# 2016_FDP_ACTIONNEUR.net
KiCad netlist of a schematic drawn in Altium Designer
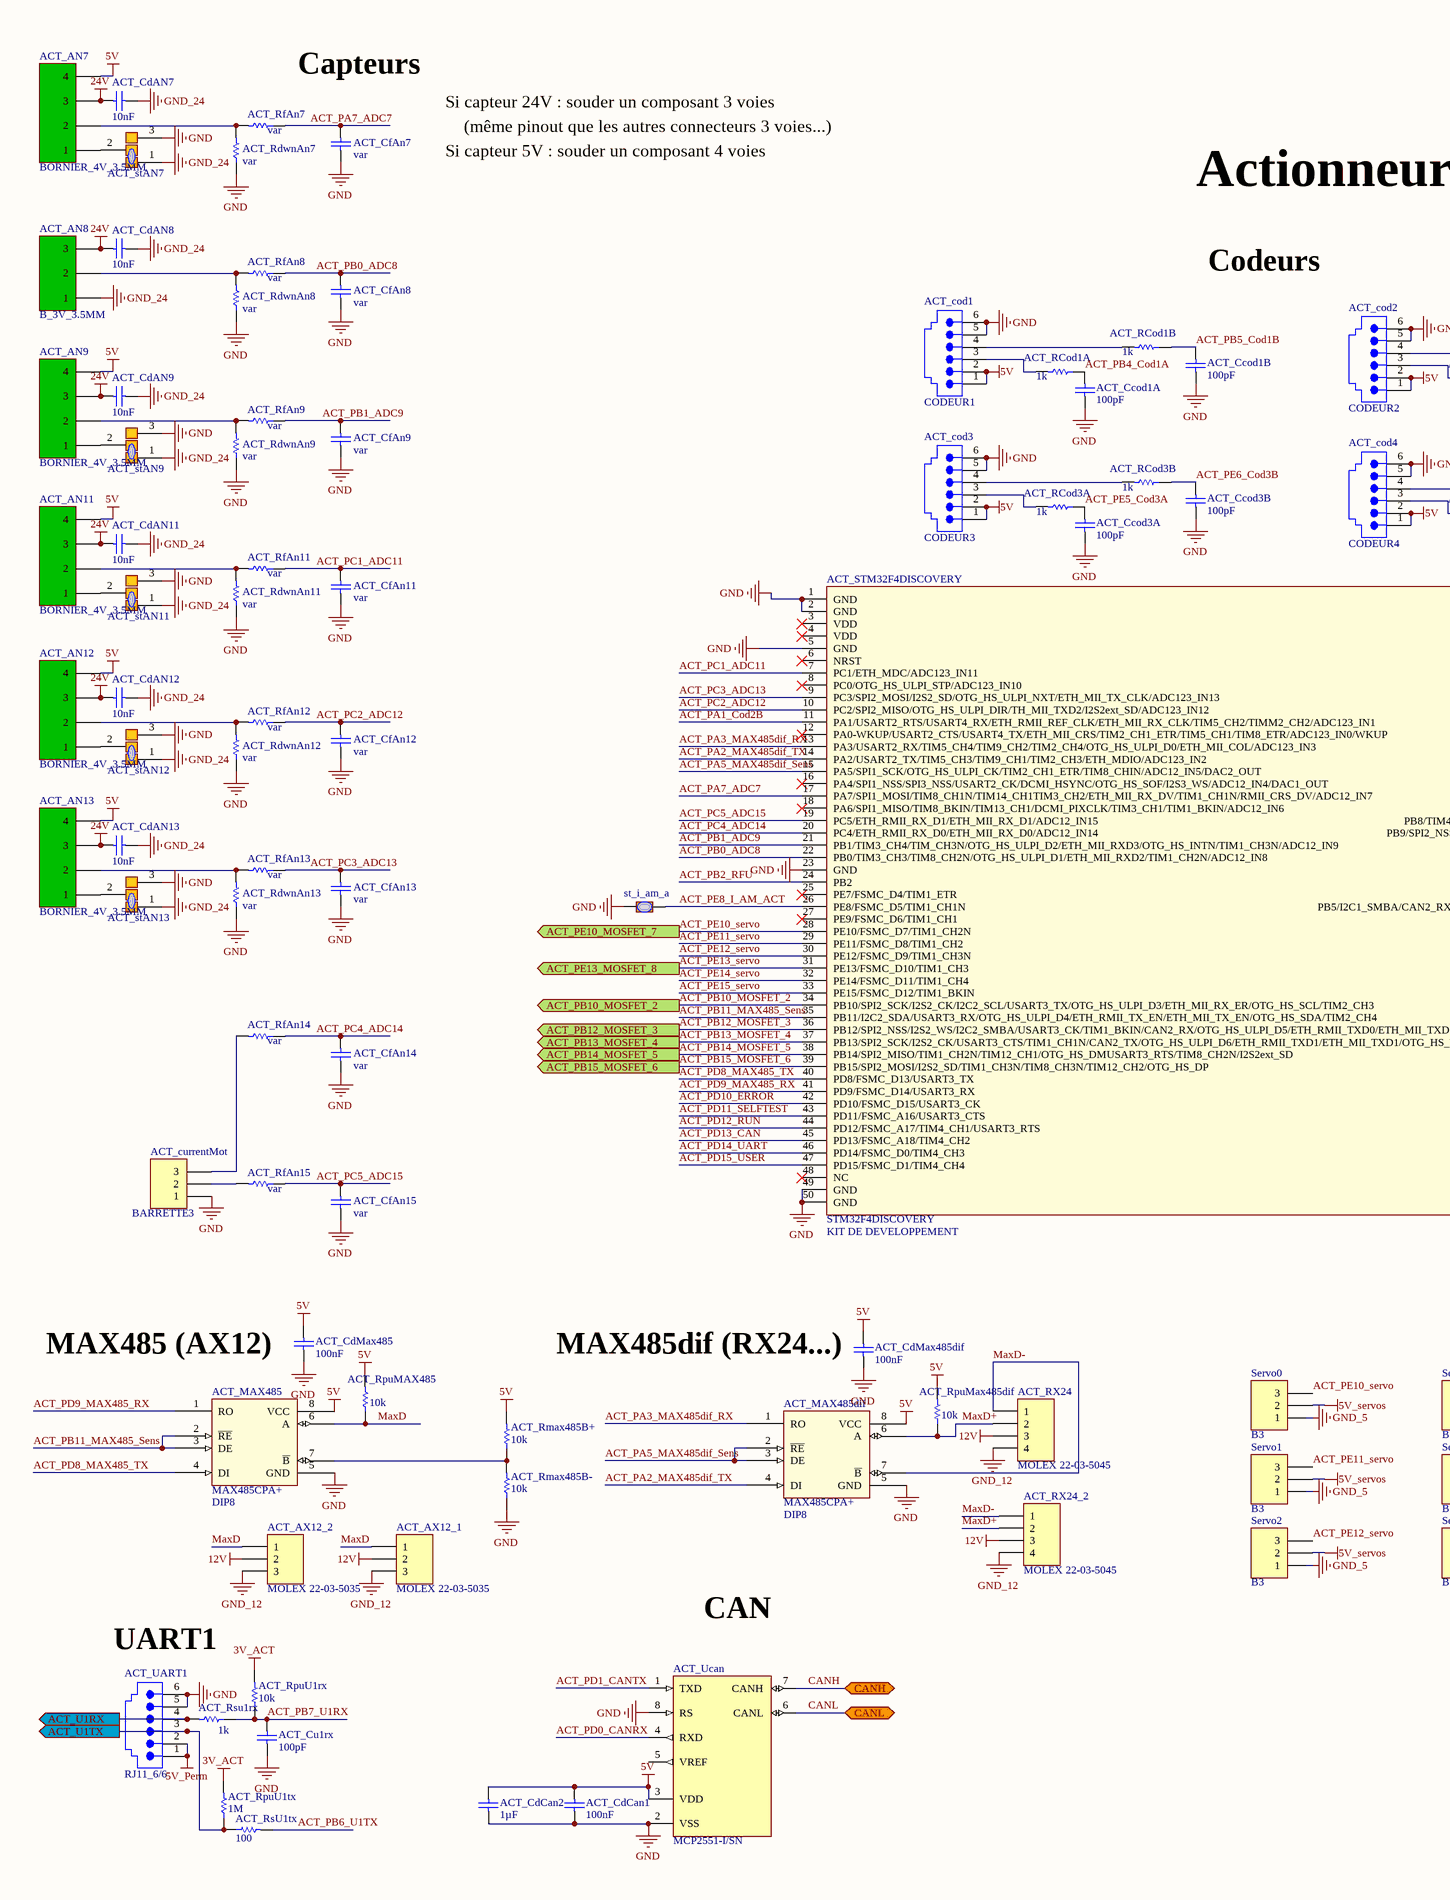
[diagram p0: 2016_FDP_ACTIONNEUR.SchDoc, left]
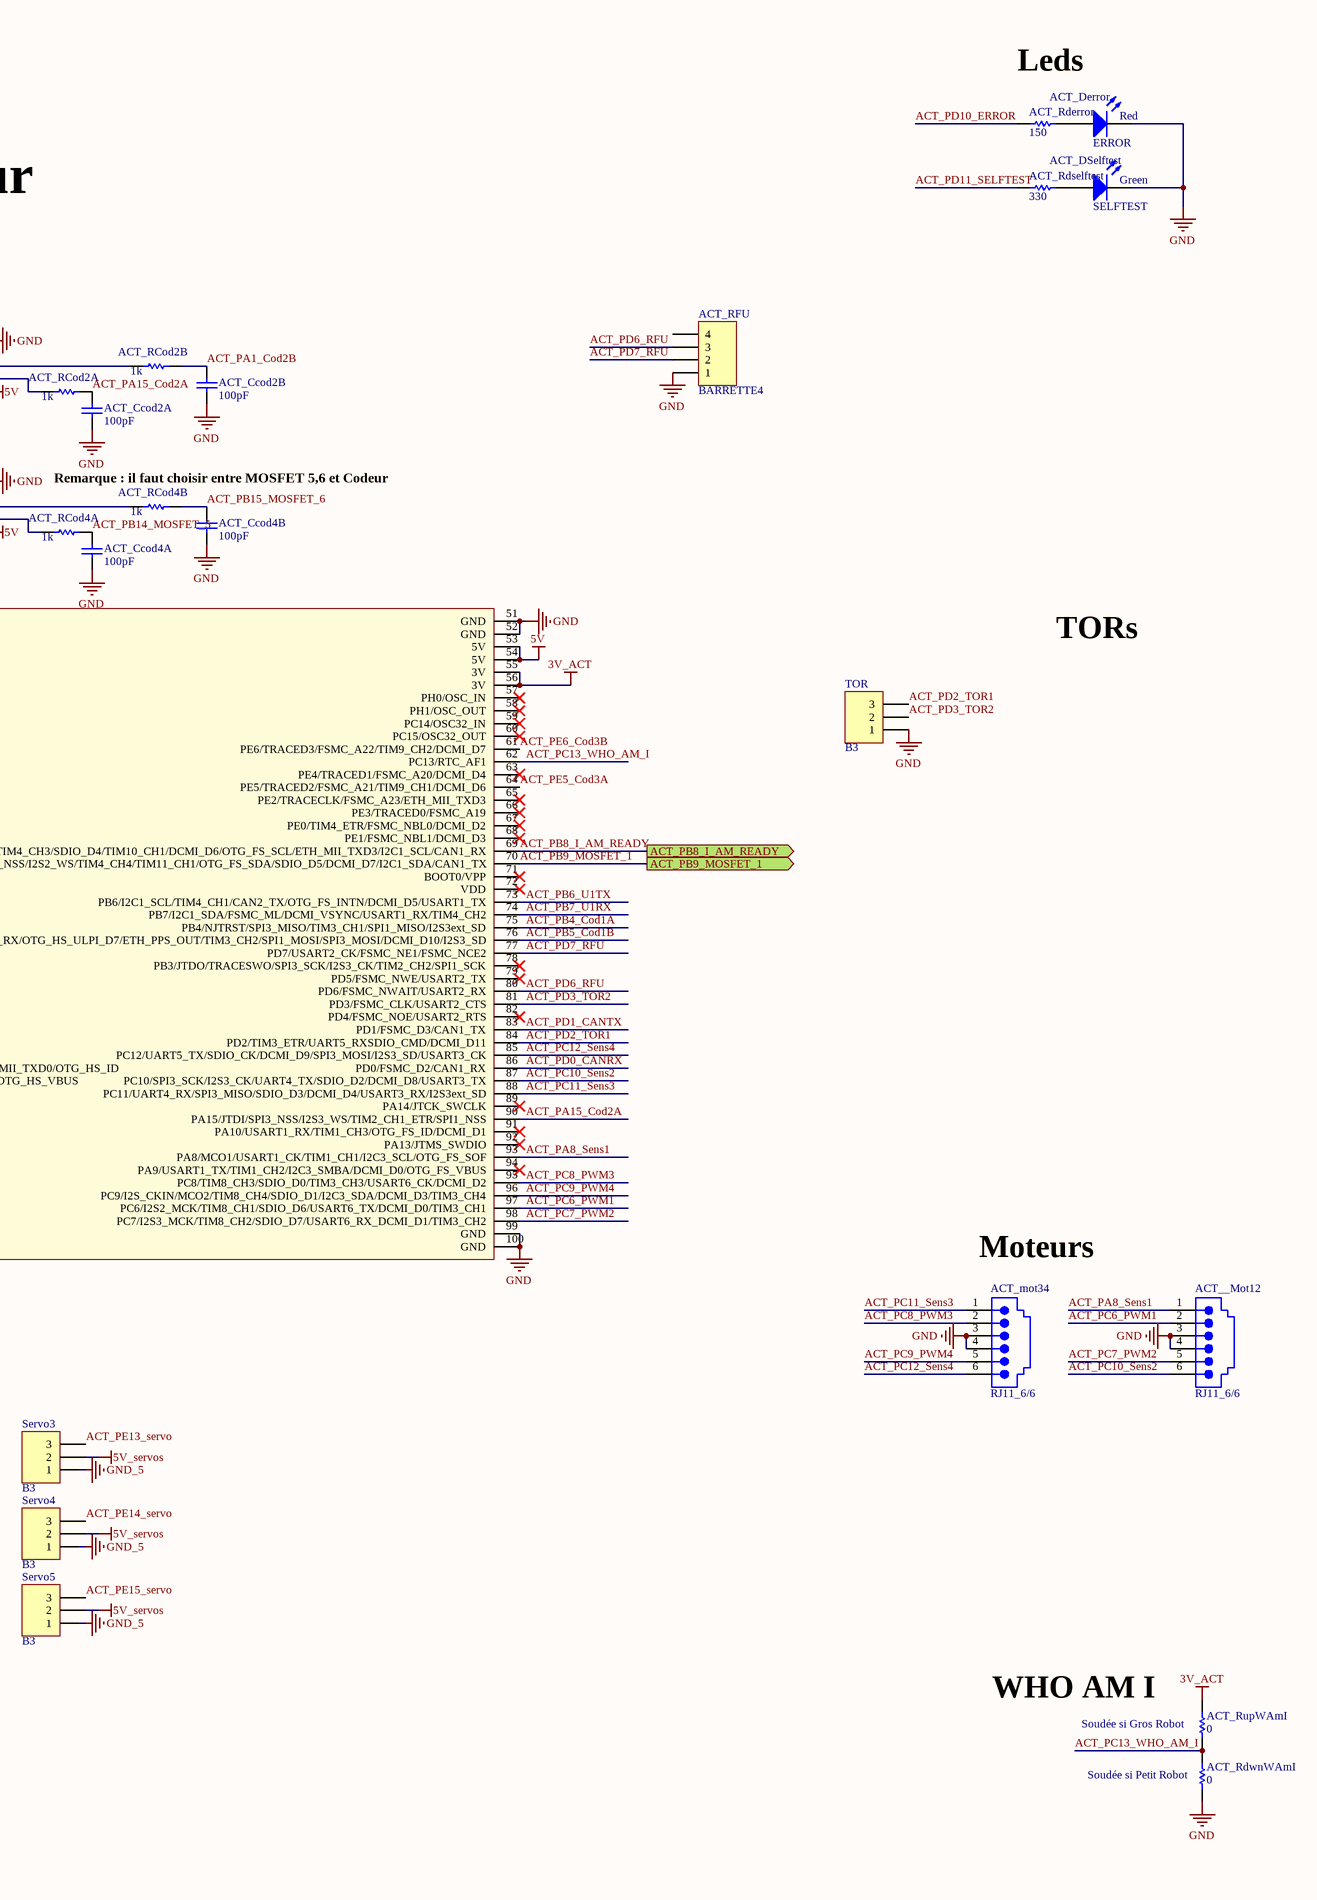
[diagram p1: 2016_FDP_ACTIONNEUR.SchDoc, right]

(export (version "E")
  (design (tool "Eeschema 10.0.6"))
  (components
    (comp (ref "ACT_AN7")
      (value "BORNIER_4V_3.5MM")
      (footprint "BORNIER_4V_3.5MM")
      (libsource (lib "Connecteur") (part "BORNIER_4V_3.5MM"))
    )
    (comp (ref "ACT_AN8")
      (value "B_3V_3.5MM")
      (footprint "BORNIER_3V_3.5MM")
      (libsource (lib "Connecteur") (part "BORNIER_3V_3.5MM"))
    )
    (comp (ref "ACT_AN9")
      (value "BORNIER_4V_3.5MM")
      (footprint "BORNIER_4V_3.5MM")
      (libsource (lib "Connecteur") (part "BORNIER_4V_3.5MM"))
    )
    (comp (ref "ACT_AN11")
      (value "BORNIER_4V_3.5MM")
      (footprint "BORNIER_4V_3.5MM")
      (libsource (lib "Connecteur") (part "BORNIER_4V_3.5MM"))
    )
    (comp (ref "ACT_AN12")
      (value "BORNIER_4V_3.5MM")
      (footprint "BORNIER_4V_3.5MM")
      (libsource (lib "Connecteur") (part "BORNIER_4V_3.5MM"))
    )
    (comp (ref "ACT_AN13")
      (value "BORNIER_4V_3.5MM")
      (footprint "BORNIER_4V_3.5MM")
      (libsource (lib "Connecteur") (part "BORNIER_4V_3.5MM"))
    )
    (comp (ref "ACT_AX12_1")
      (value "MOLEX 22-03-5035")
      (footprint "MOLEX3_2.5MM")
      (description "Header, 3-Pin")
      (fields (field (name "PUBLISHER") "Altium Limited"))
      (libsource (lib "") (part "BARRETTE3_1"))
    )
    (comp (ref "ACT_AX12_2")
      (value "MOLEX 22-03-5035")
      (footprint "MOLEX3_2.5MM")
      (description "Header, 3-Pin")
      (fields (field (name "PUBLISHER") "Altium Limited"))
      (libsource (lib "") (part "BARRETTE3_1"))
    )
    (comp (ref "ACT_Ccod1A")
      (value "100pF")
      (footprint "C0805_N")
      (description "Capacitor")
      (fields (field (name "PUBLISHER") "Altium Limited"))
      (libsource (lib "_ROBOT") (part "Condensateur"))
    )
    (comp (ref "ACT_Ccod1B")
      (value "100pF")
      (footprint "C0805_N")
      (description "Capacitor")
      (fields (field (name "PUBLISHER") "Altium Limited"))
      (libsource (lib "_ROBOT") (part "Condensateur"))
    )
    (comp (ref "ACT_Ccod2A")
      (value "100pF")
      (footprint "C0805_N")
      (description "Capacitor")
      (fields (field (name "PUBLISHER") "Altium Limited"))
      (libsource (lib "_ROBOT") (part "Condensateur"))
    )
    (comp (ref "ACT_Ccod2B")
      (value "100pF")
      (footprint "C0805_N")
      (description "Capacitor")
      (fields (field (name "PUBLISHER") "Altium Limited"))
      (libsource (lib "_ROBOT") (part "Condensateur"))
    )
    (comp (ref "ACT_Ccod3A")
      (value "100pF")
      (footprint "C0805_N")
      (description "Capacitor")
      (fields (field (name "PUBLISHER") "Altium Limited"))
      (libsource (lib "_ROBOT") (part "Condensateur"))
    )
    (comp (ref "ACT_Ccod3B")
      (value "100pF")
      (footprint "C0805_N")
      (description "Capacitor")
      (fields (field (name "PUBLISHER") "Altium Limited"))
      (libsource (lib "_ROBOT") (part "Condensateur"))
    )
    (comp (ref "ACT_Ccod4A")
      (value "100pF")
      (footprint "C0805_N")
      (description "Capacitor")
      (fields (field (name "PUBLISHER") "Altium Limited"))
      (libsource (lib "_ROBOT") (part "Condensateur"))
    )
    (comp (ref "ACT_Ccod4B")
      (value "100pF")
      (footprint "C0805_N")
      (description "Capacitor")
      (fields (field (name "PUBLISHER") "Altium Limited"))
      (libsource (lib "_ROBOT") (part "Condensateur"))
    )
    (comp (ref "ACT_CdAN7")
      (value "10nF")
      (footprint "C0805_N")
      (description "Capacitor")
      (fields (field (name "PUBLISHER") "Altium Limited"))
      (libsource (lib "_ROBOT") (part "Condensateur"))
    )
    (comp (ref "ACT_CdAN8")
      (value "10nF")
      (footprint "C0805_N")
      (description "Capacitor")
      (fields (field (name "PUBLISHER") "Altium Limited"))
      (libsource (lib "_ROBOT") (part "Condensateur"))
    )
    (comp (ref "ACT_CdAN9")
      (value "10nF")
      (footprint "C0805_N")
      (description "Capacitor")
      (fields (field (name "PUBLISHER") "Altium Limited"))
      (libsource (lib "_ROBOT") (part "Condensateur"))
    )
    (comp (ref "ACT_CdAN11")
      (value "10nF")
      (footprint "C0805_N")
      (description "Capacitor")
      (fields (field (name "PUBLISHER") "Altium Limited"))
      (libsource (lib "_ROBOT") (part "Condensateur"))
    )
    (comp (ref "ACT_CdAN12")
      (value "10nF")
      (footprint "C0805_N")
      (description "Capacitor")
      (fields (field (name "PUBLISHER") "Altium Limited"))
      (libsource (lib "_ROBOT") (part "Condensateur"))
    )
    (comp (ref "ACT_CdAN13")
      (value "10nF")
      (footprint "C0805_N")
      (description "Capacitor")
      (fields (field (name "PUBLISHER") "Altium Limited"))
      (libsource (lib "_ROBOT") (part "Condensateur"))
    )
    (comp (ref "ACT_CdCan1")
      (value "100nF")
      (footprint "C0805_N")
      (description "Capacitor")
      (fields (field (name "PUBLISHER") "Altium Limited"))
      (libsource (lib "_ROBOT") (part "Condensateur"))
    )
    (comp (ref "ACT_CdCan2")
      (value "1µF")
      (footprint "C0805_N")
      (description "Capacitor")
      (fields (field (name "PUBLISHER") "Altium Limited"))
      (libsource (lib "_ROBOT") (part "Condensateur"))
    )
    (comp (ref "ACT_CdMax485")
      (value "100nF")
      (footprint "C0805_N")
      (description "Capacitor")
      (fields (field (name "PUBLISHER") "Altium Limited"))
      (libsource (lib "_ROBOT") (part "Condensateur"))
    )
    (comp (ref "ACT_CdMax485dif")
      (value "100nF")
      (footprint "C0805_N")
      (description "Capacitor")
      (fields (field (name "PUBLISHER") "Altium Limited"))
      (libsource (lib "_ROBOT") (part "Condensateur"))
    )
    (comp (ref "ACT_CfAn7")
      (value "var")
      (footprint "C0805_N")
      (description "Capacitor")
      (fields (field (name "PUBLISHER") "Altium Limited"))
      (libsource (lib "_ROBOT") (part "Condensateur"))
    )
    (comp (ref "ACT_CfAn8")
      (value "var")
      (footprint "C0805_N")
      (description "Capacitor")
      (fields (field (name "PUBLISHER") "Altium Limited"))
      (libsource (lib "_ROBOT") (part "Condensateur"))
    )
    (comp (ref "ACT_CfAn9")
      (value "var")
      (footprint "C0805_N")
      (description "Capacitor")
      (fields (field (name "PUBLISHER") "Altium Limited"))
      (libsource (lib "_ROBOT") (part "Condensateur"))
    )
    (comp (ref "ACT_CfAn11")
      (value "var")
      (footprint "C0805_N")
      (description "Capacitor")
      (fields (field (name "PUBLISHER") "Altium Limited"))
      (libsource (lib "_ROBOT") (part "Condensateur"))
    )
    (comp (ref "ACT_CfAn12")
      (value "var")
      (footprint "C0805_N")
      (description "Capacitor")
      (fields (field (name "PUBLISHER") "Altium Limited"))
      (libsource (lib "_ROBOT") (part "Condensateur"))
    )
    (comp (ref "ACT_CfAn13")
      (value "var")
      (footprint "C0805_N")
      (description "Capacitor")
      (fields (field (name "PUBLISHER") "Altium Limited"))
      (libsource (lib "_ROBOT") (part "Condensateur"))
    )
    (comp (ref "ACT_CfAn14")
      (value "var")
      (footprint "C0805_N")
      (description "Capacitor")
      (fields (field (name "PUBLISHER") "Altium Limited"))
      (libsource (lib "_ROBOT") (part "Condensateur"))
    )
    (comp (ref "ACT_CfAn15")
      (value "var")
      (footprint "C0805_N")
      (description "Capacitor")
      (fields (field (name "PUBLISHER") "Altium Limited"))
      (libsource (lib "_ROBOT") (part "Condensateur"))
    )
    (comp (ref "ACT_cod1")
      (value "CODEUR1")
      (footprint "RJ11_6/6 - droit")
      (description "Right Angle, Standard Profile, Offset Latch DECconnect, Flangeless PCB Jack")
      (fields (field (name "PUBLISHER") "Altium Limited"))
      (libsource (lib "miniprojet") (part "RJ11_6/6"))
    )
    (comp (ref "ACT_cod2")
      (value "CODEUR2")
      (footprint "RJ11_6/6 - droit")
      (description "Right Angle, Standard Profile, Offset Latch DECconnect, Flangeless PCB Jack")
      (fields (field (name "PUBLISHER") "Altium Limited"))
      (libsource (lib "miniprojet") (part "RJ11_6/6"))
    )
    (comp (ref "ACT_cod3")
      (value "CODEUR3")
      (footprint "RJ11_6/6 - droit")
      (description "Right Angle, Standard Profile, Offset Latch DECconnect, Flangeless PCB Jack")
      (fields (field (name "PUBLISHER") "Altium Limited"))
      (libsource (lib "miniprojet") (part "RJ11_6/6"))
    )
    (comp (ref "ACT_cod4")
      (value "CODEUR4")
      (footprint "RJ11_6/6 - droit")
      (description "Right Angle, Standard Profile, Offset Latch DECconnect, Flangeless PCB Jack")
      (fields (field (name "PUBLISHER") "Altium Limited"))
      (libsource (lib "miniprojet") (part "RJ11_6/6"))
    )
    (comp (ref "ACT_Cu1rx")
      (value "100pF")
      (footprint "C0805_N")
      (description "Capacitor")
      (fields (field (name "PUBLISHER") "Altium Limited"))
      (libsource (lib "_ROBOT") (part "Condensateur"))
    )
    (comp (ref "ACT_currentMot")
      (value "BARRETTE3")
      (footprint "HE14_3")
      (description "Header, 3-Pin")
      (fields (field (name "PUBLISHER") "Altium Limited"))
      (libsource (lib "Connecteur") (part "BARRETTE3"))
    )
    (comp (ref "ACT_Derror")
      (value "ERROR")
      (footprint "LED_0805")
      (description "Typical LED")
      (fields (field (name "PUBLISHER") "Altium Limited"))
      (libsource (lib "_ROBOT") (part "LED"))
    )
    (comp (ref "ACT_DSelftest")
      (value "SELFTEST")
      (footprint "LED_0805")
      (description "Typical LED")
      (fields (field (name "PUBLISHER") "Altium Limited"))
      (libsource (lib "_ROBOT") (part "LED"))
    )
    (comp (ref "ACT_MAX485")
      (value "MAX485CPA+_DIP8")
      (footprint "SO8_N")
      (description "EMETTEUR/RECEPTEUR FAIBLE PUISSANCE DE LIAISONS RS422/RS485 - DIP8")
      (fields (field (name "TYPE") "MAX485CPA+") (field (name "PACKAGE") "DIP8"))
      (libsource (lib "circuits integres") (part "MAX485CPA+_DIP8"))
    )
    (comp (ref "ACT_MAX485dif")
      (value "MAX485CPA+_DIP8")
      (footprint "SO8_N")
      (description "EMETTEUR/RECEPTEUR FAIBLE PUISSANCE DE LIAISONS RS422/RS485 - DIP8")
      (fields (field (name "TYPE") "MAX485CPA+") (field (name "PACKAGE") "DIP8"))
      (libsource (lib "circuits integres") (part "MAX485CPA+_DIP8"))
    )
    (comp (ref "ACT_mot34")
      (value "RJ11_6/6")
      (footprint "RJ11_6/6 - droit")
      (description "Right Angle, Standard Profile, Offset Latch DECconnect, Flangeless PCB Jack")
      (fields (field (name "PUBLISHER") "Altium Limited"))
      (libsource (lib "Connecteur") (part "RJ11_6/6"))
    )
    (comp (ref "ACT_RCod1A")
      (value "1k")
      (footprint "R1206_N")
      (description "Resistor")
      (fields (field (name "PUBLISHER") "Altium Limited"))
      (libsource (lib "_ROBOT") (part "Resistor"))
    )
    (comp (ref "ACT_RCod1B")
      (value "1k")
      (footprint "R1206_N")
      (description "Resistor")
      (fields (field (name "PUBLISHER") "Altium Limited"))
      (libsource (lib "_ROBOT") (part "Resistor"))
    )
    (comp (ref "ACT_RCod2A")
      (value "1k")
      (footprint "R1206_N")
      (description "Resistor")
      (fields (field (name "PUBLISHER") "Altium Limited"))
      (libsource (lib "_ROBOT") (part "Resistor"))
    )
    (comp (ref "ACT_RCod2B")
      (value "1k")
      (footprint "R1206_N")
      (description "Resistor")
      (fields (field (name "PUBLISHER") "Altium Limited"))
      (libsource (lib "_ROBOT") (part "Resistor"))
    )
    (comp (ref "ACT_RCod3A")
      (value "1k")
      (footprint "R1206_N")
      (description "Resistor")
      (fields (field (name "PUBLISHER") "Altium Limited"))
      (libsource (lib "_ROBOT") (part "Resistor"))
    )
    (comp (ref "ACT_RCod3B")
      (value "1k")
      (footprint "R1206_N")
      (description "Resistor")
      (fields (field (name "PUBLISHER") "Altium Limited"))
      (libsource (lib "_ROBOT") (part "Resistor"))
    )
    (comp (ref "ACT_RCod4A")
      (value "1k")
      (footprint "R1206_N")
      (description "Resistor")
      (fields (field (name "PUBLISHER") "Altium Limited"))
      (libsource (lib "_ROBOT") (part "Resistor"))
    )
    (comp (ref "ACT_RCod4B")
      (value "1k")
      (footprint "R1206_N")
      (description "Resistor")
      (fields (field (name "PUBLISHER") "Altium Limited"))
      (libsource (lib "_ROBOT") (part "Resistor"))
    )
    (comp (ref "ACT_Rderror")
      (value "150")
      (footprint "R1206_N")
      (description "Resistor")
      (fields (field (name "PUBLISHER") "Altium Limited"))
      (libsource (lib "_ROBOT") (part "Resistor"))
    )
    (comp (ref "ACT_Rdselftest")
      (value "330")
      (footprint "R1206_N")
      (description "Resistor")
      (fields (field (name "PUBLISHER") "Altium Limited"))
      (libsource (lib "_ROBOT") (part "Resistor"))
    )
    (comp (ref "ACT_RdwnAn7")
      (value "var")
      (footprint "R1206_N")
      (description "Resistor")
      (fields (field (name "PUBLISHER") "Altium Limited"))
      (libsource (lib "_ROBOT") (part "Resistor"))
    )
    (comp (ref "ACT_RdwnAn8")
      (value "var")
      (footprint "R1206_N")
      (description "Resistor")
      (fields (field (name "PUBLISHER") "Altium Limited"))
      (libsource (lib "_ROBOT") (part "Resistor"))
    )
    (comp (ref "ACT_RdwnAn9")
      (value "var")
      (footprint "R1206_N")
      (description "Resistor")
      (fields (field (name "PUBLISHER") "Altium Limited"))
      (libsource (lib "_ROBOT") (part "Resistor"))
    )
    (comp (ref "ACT_RdwnAn11")
      (value "var")
      (footprint "R1206_N")
      (description "Resistor")
      (fields (field (name "PUBLISHER") "Altium Limited"))
      (libsource (lib "_ROBOT") (part "Resistor"))
    )
    (comp (ref "ACT_RdwnAn12")
      (value "var")
      (footprint "R1206_N")
      (description "Resistor")
      (fields (field (name "PUBLISHER") "Altium Limited"))
      (libsource (lib "_ROBOT") (part "Resistor"))
    )
    (comp (ref "ACT_RdwnAn13")
      (value "var")
      (footprint "R1206_N")
      (description "Resistor")
      (fields (field (name "PUBLISHER") "Altium Limited"))
      (libsource (lib "_ROBOT") (part "Resistor"))
    )
    (comp (ref "ACT_RdwnWAmI")
      (value "0")
      (footprint "R1206_N")
      (description "Resistor")
      (fields (field (name "PUBLISHER") "Altium Limited"))
      (libsource (lib "_ROBOT") (part "Resistor"))
    )
    (comp (ref "ACT_RfAn7")
      (value "var")
      (footprint "R1206_N")
      (description "Resistor")
      (fields (field (name "PUBLISHER") "Altium Limited"))
      (libsource (lib "_ROBOT") (part "Resistor"))
    )
    (comp (ref "ACT_RfAn8")
      (value "var")
      (footprint "R1206_N")
      (description "Resistor")
      (fields (field (name "PUBLISHER") "Altium Limited"))
      (libsource (lib "_ROBOT") (part "Resistor"))
    )
    (comp (ref "ACT_RfAn9")
      (value "var")
      (footprint "R1206_N")
      (description "Resistor")
      (fields (field (name "PUBLISHER") "Altium Limited"))
      (libsource (lib "_ROBOT") (part "Resistor"))
    )
    (comp (ref "ACT_RfAn11")
      (value "var")
      (footprint "R1206_N")
      (description "Resistor")
      (fields (field (name "PUBLISHER") "Altium Limited"))
      (libsource (lib "_ROBOT") (part "Resistor"))
    )
    (comp (ref "ACT_RfAn12")
      (value "var")
      (footprint "R1206_N")
      (description "Resistor")
      (fields (field (name "PUBLISHER") "Altium Limited"))
      (libsource (lib "_ROBOT") (part "Resistor"))
    )
    (comp (ref "ACT_RfAn13")
      (value "var")
      (footprint "R1206_N")
      (description "Resistor")
      (fields (field (name "PUBLISHER") "Altium Limited"))
      (libsource (lib "_ROBOT") (part "Resistor"))
    )
    (comp (ref "ACT_RfAn14")
      (value "var")
      (footprint "R1206_N")
      (description "Resistor")
      (fields (field (name "PUBLISHER") "Altium Limited"))
      (libsource (lib "_ROBOT") (part "Resistor"))
    )
    (comp (ref "ACT_RfAn15")
      (value "var")
      (footprint "R1206_N")
      (description "Resistor")
      (fields (field (name "PUBLISHER") "Altium Limited"))
      (libsource (lib "_ROBOT") (part "Resistor"))
    )
    (comp (ref "ACT_RFU")
      (value "BARRETTE4")
      (footprint "HE14_4")
      (description "Header, 4-Pin")
      (fields (field (name "PUBLISHER") "Altium Limited"))
      (libsource (lib "Connecteur") (part "BARRETTE4"))
    )
    (comp (ref "ACT_Rmax485B+")
      (value "10k")
      (footprint "R1206_N")
      (description "Resistor")
      (fields (field (name "PUBLISHER") "Altium Limited"))
      (libsource (lib "_ROBOT") (part "Resistor"))
    )
    (comp (ref "ACT_Rmax485B-")
      (value "10k")
      (footprint "R1206_N")
      (description "Resistor")
      (fields (field (name "PUBLISHER") "Altium Limited"))
      (libsource (lib "_ROBOT") (part "Resistor"))
    )
    (comp (ref "ACT_RpuMAX485")
      (value "10k")
      (footprint "R1206_N")
      (description "Resistor")
      (fields (field (name "PUBLISHER") "Altium Limited"))
      (libsource (lib "_ROBOT") (part "Resistor"))
    )
    (comp (ref "ACT_RpuMax485dif")
      (value "10k")
      (footprint "R1206_N")
      (description "Resistor")
      (fields (field (name "PUBLISHER") "Altium Limited"))
      (libsource (lib "_ROBOT") (part "Resistor"))
    )
    (comp (ref "ACT_RpuU1rx")
      (value "10k")
      (footprint "R1206_N")
      (description "Resistor")
      (fields (field (name "PUBLISHER") "Altium Limited"))
      (libsource (lib "_ROBOT") (part "Resistor"))
    )
    (comp (ref "ACT_RpuU1tx")
      (value "1M")
      (footprint "R1206_N")
      (description "Resistor")
      (fields (field (name "PUBLISHER") "Altium Limited"))
      (libsource (lib "_ROBOT") (part "Resistor"))
    )
    (comp (ref "ACT_Rsu1rx")
      (value "1k")
      (footprint "R1206_N")
      (description "Resistor")
      (fields (field (name "PUBLISHER") "Altium Limited"))
      (libsource (lib "_ROBOT") (part "Resistor"))
    )
    (comp (ref "ACT_RsU1tx")
      (value "100")
      (footprint "R1206_N")
      (description "Resistor")
      (fields (field (name "PUBLISHER") "Altium Limited"))
      (libsource (lib "_ROBOT") (part "Resistor"))
    )
    (comp (ref "ACT_RupWAmI")
      (value "0")
      (footprint "R1206_N")
      (description "Resistor")
      (fields (field (name "PUBLISHER") "Altium Limited"))
      (libsource (lib "_ROBOT") (part "Resistor"))
    )
    (comp (ref "ACT_RX24")
      (value "MOLEX 22-03-5045")
      (footprint "MOLEX4_2.5MM")
      (description "Header, 4-Pin")
      (fields (field (name "PUBLISHER") "Altium Limited"))
      (libsource (lib "") (part "BARRETTE4_1"))
    )
    (comp (ref "ACT_RX24_2")
      (value "MOLEX 22-03-5045")
      (footprint "MOLEX4_2.5MM")
      (description "Header, 4-Pin")
      (fields (field (name "PUBLISHER") "Altium Limited"))
      (libsource (lib "") (part "BARRETTE4_1"))
    )
    (comp (ref "ACT_stAN7")
      (value "strap")
      (footprint "Goutte Strap_3")
      (description "Goutte Strap_3")
      (fields (field (name "PUBLISHER") "Damien Guitton"))
      (libsource (lib "DG_Connecteur") (part "Goutte Strap_3"))
    )
    (comp (ref "ACT_stAN9")
      (value "strap")
      (footprint "Goutte Strap_3")
      (description "Goutte Strap_3")
      (fields (field (name "PUBLISHER") "Damien Guitton"))
      (libsource (lib "DG_Connecteur") (part "Goutte Strap_3"))
    )
    (comp (ref "ACT_stAN11")
      (value "strap")
      (footprint "Goutte Strap_3")
      (description "Goutte Strap_3")
      (fields (field (name "PUBLISHER") "Damien Guitton"))
      (libsource (lib "DG_Connecteur") (part "Goutte Strap_3"))
    )
    (comp (ref "ACT_stAN12")
      (value "strap")
      (footprint "Goutte Strap_3")
      (description "Goutte Strap_3")
      (fields (field (name "PUBLISHER") "Damien Guitton"))
      (libsource (lib "DG_Connecteur") (part "Goutte Strap_3"))
    )
    (comp (ref "ACT_stAN13")
      (value "strap")
      (footprint "Goutte Strap_3")
      (description "Goutte Strap_3")
      (fields (field (name "PUBLISHER") "Damien Guitton"))
      (libsource (lib "DG_Connecteur") (part "Goutte Strap_3"))
    )
    (comp (ref "ACT_STM32F4DISCOVERY")
      (value "STM32F4DISCOVERY")
      (footprint "STM32_F4DISCOVERY")
      (description "KIT DE DEVELOPPEMENT POUR MICROCONTROLEUR STM32F407VGT6")
      (fields (field (name "TYPE") "KIT DE DEVELOPPEMENT"))
      (libsource (lib "circuits integres") (part "STM32F4DISCOVERY"))
    )
    (comp (ref "ACT_UART1")
      (value "RJ11_6/6")
      (footprint "RJ11_6/6 - droit")
      (description "Right Angle, Standard Profile, Offset Latch DECconnect, Flangeless PCB Jack")
      (fields (field (name "PUBLISHER") "Altium Limited"))
      (libsource (lib "Connecteur") (part "RJ11_6/6"))
    )
    (comp (ref "ACT_Ucan")
      (value "MCP2551-I/SN")
      (footprint "SO8_N")
      (description "High-Speed CAN Transceiver, 8-Pin SOIC, Industrial Temperature")
      (fields (field (name "PUBLISHER") "Damien Guitton"))
      (libsource (lib "Circuit intégré") (part "MCP2551-I/SN"))
    )
    (comp (ref "ACT__Mot12")
      (value "RJ11_6/6")
      (footprint "RJ11_6/6 - droit")
      (description "Right Angle, Standard Profile, Offset Latch DECconnect, Flangeless PCB Jack")
      (fields (field (name "PUBLISHER") "Altium Limited"))
      (libsource (lib "Connecteur") (part "RJ11_6/6"))
    )
    (comp (ref "Servo0")
      (value "B3")
      (footprint "HE14_3")
      (description "Header, 3-Pin")
      (fields (field (name "PUBLISHER") "Altium Limited"))
      (libsource (lib "Connecteur") (part "BARRETTE3"))
    )
    (comp (ref "Servo1")
      (value "B3")
      (footprint "HE14_3")
      (description "Header, 3-Pin")
      (fields (field (name "PUBLISHER") "Altium Limited"))
      (libsource (lib "Connecteur") (part "BARRETTE3"))
    )
    (comp (ref "Servo2")
      (value "B3")
      (footprint "HE14_3")
      (description "Header, 3-Pin")
      (fields (field (name "PUBLISHER") "Altium Limited"))
      (libsource (lib "Connecteur") (part "BARRETTE3"))
    )
    (comp (ref "Servo3")
      (value "B3")
      (footprint "HE14_3")
      (description "Header, 3-Pin")
      (fields (field (name "PUBLISHER") "Altium Limited"))
      (libsource (lib "Connecteur") (part "BARRETTE3"))
    )
    (comp (ref "Servo4")
      (value "B3")
      (footprint "HE14_3")
      (description "Header, 3-Pin")
      (fields (field (name "PUBLISHER") "Altium Limited"))
      (libsource (lib "Connecteur") (part "BARRETTE3"))
    )
    (comp (ref "Servo5")
      (value "B3")
      (footprint "HE14_3")
      (description "Header, 3-Pin")
      (fields (field (name "PUBLISHER") "Altium Limited"))
      (libsource (lib "Connecteur") (part "BARRETTE3"))
    )
    (comp (ref "st_i_am_a")
      (value "Goutte Strap_2")
      (footprint "Goutte Strap_2 Pads_Clearance 0.254mm")
      (fields (field (name "PUBLISHER") "Damien Guitton"))
      (libsource (lib "DG_Connecteur") (part "Goutte Strap_2"))
    )
    (comp (ref "TOR")
      (value "B3")
      (footprint "HE14_3")
      (description "Header, 3-Pin")
      (fields (field (name "PUBLISHER") "Altium Limited"))
      (libsource (lib "Connecteur") (part "BARRETTE3"))
    )
  )
  (nets
    (net (code "1") (name "/ACT_PA1_Cod2B") (class "Default")
      (node (ref "ACT_Ccod2B") (pin "2") (pinfunction "2_2") (pintype "passive"))
      (node (ref "ACT_RCod2B") (pin "1") (pinfunction "1_1") (pintype "passive"))
      (node (ref "ACT_STM32F4DISCOVERY") (pin "11") (pinfunction "PA1/USART2_RTS/USART4_RX/ETH_RMII_REF_CLK/ETH_MII_RX_CLK/TIM5_CH2/TIMM2_CH2/ADC123_IN1_11") (pintype "passive"))
    )
    (net (code "2") (name "/ACT_PA2_MAX485dif_TX") (class "Default")
      (node (ref "ACT_MAX485dif") (pin "4") (pinfunction "DI_4") (pintype "input"))
      (node (ref "ACT_STM32F4DISCOVERY") (pin "14") (pinfunction "PA2/USART2_TX/TIM5_CH3/TIM9_CH1/TIM2_CH3/ETH_MDIO/ADC123_IN2_14") (pintype "passive"))
    )
    (net (code "3") (name "/ACT_PA3_MAX485dif_RX") (class "Default")
      (node (ref "ACT_MAX485dif") (pin "1") (pinfunction "RO_1") (pintype "tri_state"))
      (node (ref "ACT_STM32F4DISCOVERY") (pin "13") (pinfunction "PA3/USART2_RX/TIM5_CH4/TIM9_CH2/TIM2_CH4/OTG_HS_ULPI_D0/ETH_MII_COL/ADC123_IN3_13") (pintype "passive"))
    )
    (net (code "4") (name "/ACT_PA5_MAX485dif_Sens") (class "Default")
      (node (ref "ACT_MAX485dif") (pin "2") (pinfunction "~{RE}_2") (pintype "input"))
      (node (ref "ACT_MAX485dif") (pin "3") (pinfunction "DE_3") (pintype "input"))
      (node (ref "ACT_STM32F4DISCOVERY") (pin "15") (pinfunction "PA5/SPI1_SCK/OTG_HS_ULPI_CK/TIM2_CH1_ETR/TIM8_CHIN/ADC12_IN5/DAC2_OUT_15") (pintype "passive"))
    )
    (net (code "5") (name "/ACT_PA7_ADC7") (class "Default")
      (node (ref "ACT_CfAn7") (pin "2") (pinfunction "2_2") (pintype "passive"))
      (node (ref "ACT_RfAn7") (pin "1") (pinfunction "1_1") (pintype "passive"))
      (node (ref "ACT_STM32F4DISCOVERY") (pin "17") (pinfunction "PA7/SPI1_MOSI/TIM8_CH1N/TIM14_CH1TIM3_CH2/ETH_MII_RX_DV/TIM1_CH1N/RMII_CRS_DV/ADC12_IN7_17") (pintype "passive"))
    )
    (net (code "6") (name "/ACT_PA8_Sens1") (class "Default")
      (node (ref "ACT_STM32F4DISCOVERY") (pin "93") (pinfunction "PA8/MCO1/USART1_CK/TIM1_CH1/I2C3_SCL/OTG_FS_SOF_93") (pintype "passive"))
      (node (ref "ACT__Mot12") (pin "1") (pinfunction "1_1") (pintype "passive"))
    )
    (net (code "7") (name "/ACT_PA15_Cod2A") (class "Default")
      (node (ref "ACT_Ccod2A") (pin "2") (pinfunction "2_2") (pintype "passive"))
      (node (ref "ACT_RCod2A") (pin "1") (pinfunction "1_1") (pintype "passive"))
      (node (ref "ACT_STM32F4DISCOVERY") (pin "90") (pinfunction "PA15/JTDI/SPI3_NSS/I2S3_WS/TIM2_CH1_ETR/SPI1_NSS_90") (pintype "passive"))
    )
    (net (code "8") (name "/ACT_PB0_ADC8") (class "Default")
      (node (ref "ACT_CfAn8") (pin "2") (pinfunction "2_2") (pintype "passive"))
      (node (ref "ACT_RfAn8") (pin "1") (pinfunction "1_1") (pintype "passive"))
      (node (ref "ACT_STM32F4DISCOVERY") (pin "22") (pinfunction "PB0/TIM3_CH3/TIM8_CH2N/OTG_HS_ULPI_D1/ETH_MII_RXD2/TIM1_CH2N/ADC12_IN8_22") (pintype "passive"))
    )
    (net (code "9") (name "/ACT_PB1_ADC9") (class "Default")
      (node (ref "ACT_CfAn9") (pin "2") (pinfunction "2_2") (pintype "passive"))
      (node (ref "ACT_RfAn9") (pin "1") (pinfunction "1_1") (pintype "passive"))
      (node (ref "ACT_STM32F4DISCOVERY") (pin "21") (pinfunction "PB1/TIM3_CH4/TIM_CH3N/OTG_HS_ULPI_D2/ETH_MII_RXD3/OTG_HS_INTN/TIM1_CH3N/ADC12_IN9_21") (pintype "passive"))
    )
    (net (code "10") (name "/ACT_PB2_RFU") (class "Default")
      (node (ref "ACT_STM32F4DISCOVERY") (pin "24") (pinfunction "PB2_24") (pintype "passive"))
    )
    (net (code "11") (name "/ACT_PB4_Cod1A") (class "Default")
      (node (ref "ACT_Ccod1A") (pin "2") (pinfunction "2_2") (pintype "passive"))
      (node (ref "ACT_RCod1A") (pin "1") (pinfunction "1_1") (pintype "passive"))
      (node (ref "ACT_STM32F4DISCOVERY") (pin "75") (pinfunction "PB4/NJTRST/SPI3_MISO/TIM3_CH1/SPI1_MISO/I2S3ext_SD_75") (pintype "passive"))
    )
    (net (code "12") (name "/ACT_PB5_Cod1B") (class "Default")
      (node (ref "ACT_Ccod1B") (pin "2") (pinfunction "2_2") (pintype "passive"))
      (node (ref "ACT_RCod1B") (pin "1") (pinfunction "1_1") (pintype "passive"))
      (node (ref "ACT_STM32F4DISCOVERY") (pin "76") (pinfunction "PB5/I2C1_SMBA/CAN2_RX/OTG_HS_ULPI_D7/ETH_PPS_OUT/TIM3_CH2/SPI1_MOSI/SPI3_MOSI/DCMI_D10/I2S3_SD_76") (pintype "passive"))
    )
    (net (code "13") (name "/ACT_PB6_U1TX") (class "Default")
      (node (ref "ACT_RsU1tx") (pin "2") (pinfunction "2_2") (pintype "passive"))
      (node (ref "ACT_STM32F4DISCOVERY") (pin "73") (pinfunction "PB6/I2C1_SCL/TIM4_CH1/CAN2_TX/OTG_FS_INTN/DCMI_D5/USART1_TX_73") (pintype "passive"))
    )
    (net (code "14") (name "/ACT_PB7_U1RX") (class "Default")
      (node (ref "ACT_Cu1rx") (pin "2") (pinfunction "2_2") (pintype "passive"))
      (node (ref "ACT_RpuU1rx") (pin "1") (pinfunction "1_1") (pintype "passive"))
      (node (ref "ACT_Rsu1rx") (pin "1") (pinfunction "1_1") (pintype "passive"))
      (node (ref "ACT_STM32F4DISCOVERY") (pin "74") (pinfunction "PB7/I2C1_SDA/FSMC_ML/DCMI_VSYNC/USART1_RX/TIM4_CH2_74") (pintype "passive"))
    )
    (net (code "15") (name "/ACT_PB8_I_AM_READY") (class "Default")
      (node (ref "ACT_STM32F4DISCOVERY") (pin "69") (pinfunction "PB8/TIM4_CH3/SDIO_D4/TIM10_CH1/DCMI_D6/OTG_FS_SCL/ETH_MII_TXD3/I2C1_SCL/CAN1_RX_69") (pintype "passive"))
    )
    (net (code "16") (name "/ACT_PB9_MOSFET_1") (class "Default")
      (node (ref "ACT_STM32F4DISCOVERY") (pin "70") (pinfunction "PB9/SPI2_NSS/I2S2_WS/TIM4_CH4/TIM11_CH1/OTG_FS_SDA/SDIO_D5/DCMI_D7/I2C1_SDA/CAN1_TX_70") (pintype "passive"))
    )
    (net (code "17") (name "/ACT_PB10_MOSFET_2") (class "Default")
      (node (ref "ACT_STM32F4DISCOVERY") (pin "34") (pinfunction "PB10/SPI2_SCK/I2S2_CK/I2C2_SCL/USART3_TX/OTG_HS_ULPI_D3/ETH_MII_RX_ER/OTG_HS_SCL/TIM2_CH3_34") (pintype "passive"))
    )
    (net (code "18") (name "/ACT_PB11_MAX485_Sens") (class "Default")
      (node (ref "ACT_MAX485") (pin "2") (pinfunction "~{RE}_2") (pintype "input"))
      (node (ref "ACT_MAX485") (pin "3") (pinfunction "DE_3") (pintype "input"))
      (node (ref "ACT_STM32F4DISCOVERY") (pin "35") (pinfunction "PB11/I2C2_SDA/USART3_RX/OTG_HS_ULPI_D4/ETH_RMII_TX_EN/ETH_MII_TX_EN/OTG_HS_SDA/TIM2_CH4_35") (pintype "passive"))
    )
    (net (code "19") (name "/ACT_PB12_MOSFET_3") (class "Default")
      (node (ref "ACT_STM32F4DISCOVERY") (pin "36") (pinfunction "PB12/SPI2_NSS/I2S2_WS/I2C2_SMBA/USART3_CK/TIM1_BKIN/CAN2_RX/OTG_HS_ULPI_D5/ETH_RMII_TXD0/ETH_MII_TXD0/OTG_HS_ID_36") (pintype "passive"))
    )
    (net (code "20") (name "/ACT_PB13_MOSFET_4") (class "Default")
      (node (ref "ACT_STM32F4DISCOVERY") (pin "37") (pinfunction "PB13/SPI2_SCK/I2S2_CK/USART3_CTS/TIM1_CH1N/CAN2_TX/OTG_HS_ULPI_D6/ETH_RMII_TXD1/ETH_MII_TXD1/OTG_HS_VBUS_37") (pintype "passive"))
    )
    (net (code "21") (name "/ACT_PB14_MOSFET_5") (class "Default")
      (node (ref "ACT_Ccod4A") (pin "2") (pinfunction "2_2") (pintype "passive"))
      (node (ref "ACT_RCod4A") (pin "1") (pinfunction "1_1") (pintype "passive"))
      (node (ref "ACT_STM32F4DISCOVERY") (pin "38") (pinfunction "PB14/SPI2_MISO/TIM1_CH2N/TIM12_CH1/OTG_HS_DMUSART3_RTS/TIM8_CH2N/I2S2ext_SD_38") (pintype "passive"))
    )
    (net (code "22") (name "/ACT_PB15_MOSFET_6") (class "Default")
      (node (ref "ACT_Ccod4B") (pin "2") (pinfunction "2_2") (pintype "passive"))
      (node (ref "ACT_RCod4B") (pin "1") (pinfunction "1_1") (pintype "passive"))
      (node (ref "ACT_STM32F4DISCOVERY") (pin "39") (pinfunction "PB15/SPI2_MOSI/I2S2_SD/TIM1_CH3N/TIM8_CH3N/TIM12_CH2/OTG_HS_DP_39") (pintype "passive"))
    )
    (net (code "23") (name "/ACT_PC1_ADC11") (class "Default")
      (node (ref "ACT_CfAn11") (pin "2") (pinfunction "2_2") (pintype "passive"))
      (node (ref "ACT_RfAn11") (pin "1") (pinfunction "1_1") (pintype "passive"))
      (node (ref "ACT_STM32F4DISCOVERY") (pin "7") (pinfunction "PC1/ETH_MDC/ADC123_IN11_7") (pintype "passive"))
    )
    (net (code "24") (name "/ACT_PC2_ADC12") (class "Default")
      (node (ref "ACT_CfAn12") (pin "2") (pinfunction "2_2") (pintype "passive"))
      (node (ref "ACT_RfAn12") (pin "1") (pinfunction "1_1") (pintype "passive"))
      (node (ref "ACT_STM32F4DISCOVERY") (pin "10") (pinfunction "PC2/SPI2_MISO/OTG_HS_ULPI_DIR/TH_MII_TXD2/I2S2ext_SD/ADC123_IN12_10") (pintype "passive"))
    )
    (net (code "25") (name "/ACT_PC3_ADC13") (class "Default")
      (node (ref "ACT_CfAn13") (pin "2") (pinfunction "2_2") (pintype "passive"))
      (node (ref "ACT_RfAn13") (pin "1") (pinfunction "1_1") (pintype "passive"))
      (node (ref "ACT_STM32F4DISCOVERY") (pin "9") (pinfunction "PC3/SPI2_MOSI/I2S2_SD/OTG_HS_ULPI_NXT/ETH_MII_TX_CLK/ADC123_IN13_9") (pintype "passive"))
    )
    (net (code "26") (name "/ACT_PC4_ADC14") (class "Default")
      (node (ref "ACT_CfAn14") (pin "2") (pinfunction "2_2") (pintype "passive"))
      (node (ref "ACT_RfAn14") (pin "1") (pinfunction "1_1") (pintype "passive"))
      (node (ref "ACT_STM32F4DISCOVERY") (pin "20") (pinfunction "PC4/ETH_RMII_RX_D0/ETH_MII_RX_D0/ADC12_IN14_20") (pintype "passive"))
    )
    (net (code "27") (name "/ACT_PC5_ADC15") (class "Default")
      (node (ref "ACT_CfAn15") (pin "2") (pinfunction "2_2") (pintype "passive"))
      (node (ref "ACT_RfAn15") (pin "1") (pinfunction "1_1") (pintype "passive"))
      (node (ref "ACT_STM32F4DISCOVERY") (pin "19") (pinfunction "PC5/ETH_RMII_RX_D1/ETH_MII_RX_D1/ADC12_IN15_19") (pintype "passive"))
    )
    (net (code "28") (name "/ACT_PC6_PWM1") (class "Default")
      (node (ref "ACT_STM32F4DISCOVERY") (pin "97") (pinfunction "PC6/I2S2_MCK/TIM8_CH1/SDIO_D6/USART6_TX/DCMI_D0/TIM3_CH1_97") (pintype "passive"))
      (node (ref "ACT__Mot12") (pin "2") (pinfunction "2_2") (pintype "passive"))
    )
    (net (code "29") (name "/ACT_PC7_PWM2") (class "Default")
      (node (ref "ACT_STM32F4DISCOVERY") (pin "98") (pinfunction "PC7/I2S3_MCK/TIM8_CH2/SDIO_D7/USART6_RX_DCMI_D1/TIM3_CH2_98") (pintype "passive"))
      (node (ref "ACT__Mot12") (pin "5") (pinfunction "5_5") (pintype "passive"))
    )
    (net (code "30") (name "/ACT_PC8_PWM3") (class "Default")
      (node (ref "ACT_STM32F4DISCOVERY") (pin "95") (pinfunction "PC8/TIM8_CH3/SDIO_D0/TIM3_CH3/USART6_CK/DCMI_D2_95") (pintype "passive"))
      (node (ref "ACT_mot34") (pin "2") (pinfunction "2_2") (pintype "passive"))
    )
    (net (code "31") (name "/ACT_PC9_PWM4") (class "Default")
      (node (ref "ACT_STM32F4DISCOVERY") (pin "96") (pinfunction "PC9/I2S_CKIN/MCO2/TIM8_CH4/SDIO_D1/I2C3_SDA/DCMI_D3/TIM3_CH4_96") (pintype "passive"))
      (node (ref "ACT_mot34") (pin "5") (pinfunction "5_5") (pintype "passive"))
    )
    (net (code "32") (name "/ACT_PC10_Sens2") (class "Default")
      (node (ref "ACT_STM32F4DISCOVERY") (pin "87") (pinfunction "PC10/SPI3_SCK/I2S3_CK/UART4_TX/SDIO_D2/DCMI_D8/USART3_TX_87") (pintype "passive"))
      (node (ref "ACT__Mot12") (pin "6") (pinfunction "6_6") (pintype "passive"))
    )
    (net (code "33") (name "/ACT_PC11_Sens3") (class "Default")
      (node (ref "ACT_STM32F4DISCOVERY") (pin "88") (pinfunction "PC11/UART4_RX/SPI3_MISO/SDIO_D3/DCMI_D4/USART3_RX/I2S3ext_SD_88") (pintype "passive"))
      (node (ref "ACT_mot34") (pin "1") (pinfunction "1_1") (pintype "passive"))
    )
    (net (code "34") (name "/ACT_PC12_Sens4") (class "Default")
      (node (ref "ACT_STM32F4DISCOVERY") (pin "85") (pinfunction "PC12/UART5_TX/SDIO_CK/DCMI_D9/SPI3_MOSI/I2S3_SD/USART3_CK_85") (pintype "passive"))
      (node (ref "ACT_mot34") (pin "6") (pinfunction "6_6") (pintype "passive"))
    )
    (net (code "35") (name "/ACT_PC13_WHO_AM_I") (class "Default")
      (node (ref "ACT_RdwnWAmI") (pin "2") (pinfunction "2_2") (pintype "passive"))
      (node (ref "ACT_RupWAmI") (pin "1") (pinfunction "1_1") (pintype "passive"))
      (node (ref "ACT_STM32F4DISCOVERY") (pin "62") (pinfunction "PC13/RTC_AF1_62") (pintype "passive"))
    )
    (net (code "36") (name "/ACT_PD0_CANRX") (class "Default")
      (node (ref "ACT_STM32F4DISCOVERY") (pin "86") (pinfunction "PD0/FSMC_D2/CAN1_RX_86") (pintype "passive"))
      (node (ref "ACT_Ucan") (pin "4") (pinfunction "RXD_4") (pintype "output"))
    )
    (net (code "37") (name "/ACT_PD1_CANTX") (class "Default")
      (node (ref "ACT_STM32F4DISCOVERY") (pin "83") (pinfunction "PD1/FSMC_D3/CAN1_TX_83") (pintype "passive"))
      (node (ref "ACT_Ucan") (pin "1") (pinfunction "TXD_1") (pintype "input"))
    )
    (net (code "38") (name "/ACT_PD2_TOR1") (class "Default")
      (node (ref "ACT_STM32F4DISCOVERY") (pin "84") (pinfunction "PD2/TIM3_ETR/UART5_RXSDIO_CMD/DCMI_D11_84") (pintype "passive"))
      (node (ref "TOR") (pin "3") (pinfunction "3_3") (pintype "passive"))
    )
    (net (code "39") (name "/ACT_PD3_TOR2") (class "Default")
      (node (ref "ACT_STM32F4DISCOVERY") (pin "81") (pinfunction "PD3/FSMC_CLK/USART2_CTS_81") (pintype "passive"))
      (node (ref "TOR") (pin "2") (pinfunction "2_2") (pintype "passive"))
    )
    (net (code "40") (name "/ACT_PD6_RFU") (class "Default")
      (node (ref "ACT_RFU") (pin "3") (pinfunction "3_3") (pintype "passive"))
      (node (ref "ACT_STM32F4DISCOVERY") (pin "80") (pinfunction "PD6/FSMC_NWAIT/USART2_RX_80") (pintype "passive"))
    )
    (net (code "41") (name "/ACT_PD7_RFU") (class "Default")
      (node (ref "ACT_RFU") (pin "2") (pinfunction "2_2") (pintype "passive"))
      (node (ref "ACT_STM32F4DISCOVERY") (pin "77") (pinfunction "PD7/USART2_CK/FSMC_NE1/FSMC_NCE2_77") (pintype "passive"))
    )
    (net (code "42") (name "/ACT_PD8_MAX485_TX") (class "Default")
      (node (ref "ACT_MAX485") (pin "4") (pinfunction "DI_4") (pintype "input"))
      (node (ref "ACT_STM32F4DISCOVERY") (pin "40") (pinfunction "PD8/FSMC_D13/USART3_TX_40") (pintype "passive"))
    )
    (net (code "43") (name "/ACT_PD9_MAX485_RX") (class "Default")
      (node (ref "ACT_MAX485") (pin "1") (pinfunction "RO_1") (pintype "tri_state"))
      (node (ref "ACT_STM32F4DISCOVERY") (pin "41") (pinfunction "PD9/FSMC_D14/USART3_RX_41") (pintype "passive"))
    )
    (net (code "44") (name "/ACT_PD10_ERROR") (class "Default")
      (node (ref "ACT_Rderror") (pin "1") (pinfunction "1_1") (pintype "passive"))
      (node (ref "ACT_STM32F4DISCOVERY") (pin "42") (pinfunction "PD10/FSMC_D15/USART3_CK_42") (pintype "passive"))
    )
    (net (code "45") (name "/ACT_PD11_SELFTEST") (class "Default")
      (node (ref "ACT_Rdselftest") (pin "1") (pinfunction "1_1") (pintype "passive"))
      (node (ref "ACT_STM32F4DISCOVERY") (pin "43") (pinfunction "PD11/FSMC_A16/USART3_CTS_43") (pintype "passive"))
    )
    (net (code "46") (name "/ACT_PD12_RUN") (class "Default")
      (node (ref "ACT_STM32F4DISCOVERY") (pin "44") (pinfunction "PD12/FSMC_A17/TIM4_CH1/USART3_RTS_44") (pintype "passive"))
    )
    (net (code "47") (name "/ACT_PD13_CAN") (class "Default")
      (node (ref "ACT_STM32F4DISCOVERY") (pin "45") (pinfunction "PD13/FSMC_A18/TIM4_CH2_45") (pintype "passive"))
    )
    (net (code "48") (name "/ACT_PD14_UART") (class "Default")
      (node (ref "ACT_STM32F4DISCOVERY") (pin "46") (pinfunction "PD14/FSMC_D0/TIM4_CH3_46") (pintype "passive"))
    )
    (net (code "49") (name "/ACT_PD15_USER") (class "Default")
      (node (ref "ACT_STM32F4DISCOVERY") (pin "47") (pinfunction "PD15/FSMC_D1/TIM4_CH4_47") (pintype "passive"))
    )
    (net (code "50") (name "/ACT_PE5_Cod3A") (class "Default")
      (node (ref "ACT_Ccod3A") (pin "2") (pinfunction "2_2") (pintype "passive"))
      (node (ref "ACT_RCod3A") (pin "1") (pinfunction "1_1") (pintype "passive"))
      (node (ref "ACT_STM32F4DISCOVERY") (pin "64") (pinfunction "PE5/TRACED2/FSMC_A21/TIM9_CH1/DCMI_D6_64") (pintype "passive"))
    )
    (net (code "51") (name "/ACT_PE6_Cod3B") (class "Default")
      (node (ref "ACT_Ccod3B") (pin "2") (pinfunction "2_2") (pintype "passive"))
      (node (ref "ACT_RCod3B") (pin "1") (pinfunction "1_1") (pintype "passive"))
      (node (ref "ACT_STM32F4DISCOVERY") (pin "61") (pinfunction "PE6/TRACED3/FSMC_A22/TIM9_CH2/DCMI_D7_61") (pintype "passive"))
    )
    (net (code "52") (name "/ACT_PE8_I_AM_ACT") (class "Default")
      (node (ref "ACT_STM32F4DISCOVERY") (pin "26") (pinfunction "PE8/FSMC_D5/TIM1_CH1N_26") (pintype "passive"))
      (node (ref "st_i_am_a") (pin "2") (pinfunction "2_2") (pintype "passive"))
    )
    (net (code "53") (name "/ACT_PE10_servo") (class "Default")
      (node (ref "ACT_STM32F4DISCOVERY") (pin "28") (pinfunction "PE10/FSMC_D7/TIM1_CH2N_28") (pintype "passive"))
      (node (ref "Servo0") (pin "3") (pinfunction "3_3") (pintype "passive"))
    )
    (net (code "54") (name "/ACT_PE11_servo") (class "Default")
      (node (ref "ACT_STM32F4DISCOVERY") (pin "29") (pinfunction "PE11/FSMC_D8/TIM1_CH2_29") (pintype "passive"))
      (node (ref "Servo1") (pin "3") (pinfunction "3_3") (pintype "passive"))
    )
    (net (code "55") (name "/ACT_PE12_servo") (class "Default")
      (node (ref "ACT_STM32F4DISCOVERY") (pin "30") (pinfunction "PE12/FSMC_D9/TIM1_CH3N_30") (pintype "passive"))
      (node (ref "Servo2") (pin "3") (pinfunction "3_3") (pintype "passive"))
    )
    (net (code "56") (name "/ACT_PE13_servo") (class "Default")
      (node (ref "ACT_STM32F4DISCOVERY") (pin "31") (pinfunction "PE13/FSMC_D10/TIM1_CH3_31") (pintype "passive"))
      (node (ref "Servo3") (pin "3") (pinfunction "3_3") (pintype "passive"))
    )
    (net (code "57") (name "/ACT_PE14_servo") (class "Default")
      (node (ref "ACT_STM32F4DISCOVERY") (pin "32") (pinfunction "PE14/FSMC_D11/TIM1_CH4_32") (pintype "passive"))
      (node (ref "Servo4") (pin "3") (pinfunction "3_3") (pintype "passive"))
    )
    (net (code "58") (name "/ACT_PE15_servo") (class "Default")
      (node (ref "ACT_STM32F4DISCOVERY") (pin "33") (pinfunction "PE15/FSMC_D12/TIM1_BKIN_33") (pintype "passive"))
      (node (ref "Servo5") (pin "3") (pinfunction "3_3") (pintype "passive"))
    )
    (net (code "59") (name "/ACT_U1RX") (class "Default")
      (node (ref "ACT_Rsu1rx") (pin "2") (pinfunction "2_2") (pintype "passive"))
      (node (ref "ACT_UART1") (pin "4") (pinfunction "4_4") (pintype "passive"))
    )
    (net (code "60") (name "/ACT_U1TX") (class "Default")
      (node (ref "ACT_RpuU1tx") (pin "1") (pinfunction "1_1") (pintype "passive"))
      (node (ref "ACT_RsU1tx") (pin "1") (pinfunction "1_1") (pintype "passive"))
      (node (ref "ACT_UART1") (pin "3") (pinfunction "3_3") (pintype "passive"))
    )
    (net (code "61") (name "/CANH") (class "Default")
      (node (ref "ACT_Ucan") (pin "7") (pinfunction "CANH_7") (pintype "bidirectional"))
    )
    (net (code "62") (name "/CANL") (class "Default")
      (node (ref "ACT_Ucan") (pin "6") (pinfunction "CANL_6") (pintype "bidirectional"))
    )
    (net (code "63") (name "/MaxD") (class "Default")
      (node (ref "ACT_AX12_1") (pin "1") (pinfunction "1_1") (pintype "passive"))
      (node (ref "ACT_AX12_2") (pin "1") (pinfunction "1_1") (pintype "passive"))
      (node (ref "ACT_MAX485") (pin "6") (pinfunction "A_6") (pintype "bidirectional"))
      (node (ref "ACT_RpuMAX485") (pin "1") (pinfunction "1_1") (pintype "passive"))
    )
    (net (code "64") (name "/MaxD+") (class "Default")
      (node (ref "ACT_MAX485dif") (pin "6") (pinfunction "A_6") (pintype "bidirectional"))
      (node (ref "ACT_RX24") (pin "2") (pinfunction "2_2") (pintype "passive"))
      (node (ref "ACT_RX24_2") (pin "2") (pinfunction "2_2") (pintype "passive"))
      (node (ref "ACT_RpuMax485dif") (pin "1") (pinfunction "1_1") (pintype "passive"))
    )
    (net (code "65") (name "/MaxD-") (class "Default")
      (node (ref "ACT_MAX485dif") (pin "7") (pinfunction "~{B}_7") (pintype "bidirectional"))
      (node (ref "ACT_RX24") (pin "1") (pinfunction "1_1") (pintype "passive"))
      (node (ref "ACT_RX24_2") (pin "1") (pinfunction "1_1") (pintype "passive"))
    )
    (net (code "66") (name "3V_ACT") (class "Default")
      (node (ref "ACT_RpuU1rx") (pin "2") (pinfunction "2_2") (pintype "passive"))
      (node (ref "ACT_RpuU1tx") (pin "2") (pinfunction "2_2") (pintype "passive"))
      (node (ref "ACT_RupWAmI") (pin "2") (pinfunction "2_2") (pintype "passive"))
      (node (ref "ACT_STM32F4DISCOVERY") (pin "55") (pinfunction "3V_55") (pintype "passive"))
      (node (ref "ACT_STM32F4DISCOVERY") (pin "56") (pinfunction "3V_56") (pintype "passive"))
    )
    (net (code "67") (name "5V") (class "Default")
      (node (ref "ACT_AN11") (pin "4") (pinfunction "4_4") (pintype "passive"))
      (node (ref "ACT_AN12") (pin "4") (pinfunction "4_4") (pintype "passive"))
      (node (ref "ACT_AN13") (pin "4") (pinfunction "4_4") (pintype "passive"))
      (node (ref "ACT_AN7") (pin "4") (pinfunction "4_4") (pintype "passive"))
      (node (ref "ACT_AN9") (pin "4") (pinfunction "4_4") (pintype "passive"))
      (node (ref "ACT_CdCan1") (pin "2") (pinfunction "2_2") (pintype "passive"))
      (node (ref "ACT_CdCan2") (pin "2") (pinfunction "2_2") (pintype "passive"))
      (node (ref "ACT_CdMax485") (pin "2") (pinfunction "2_2") (pintype "passive"))
      (node (ref "ACT_CdMax485dif") (pin "2") (pinfunction "2_2") (pintype "passive"))
      (node (ref "ACT_MAX485") (pin "8") (pinfunction "VCC_8") (pintype "passive"))
      (node (ref "ACT_MAX485dif") (pin "8") (pinfunction "VCC_8") (pintype "passive"))
      (node (ref "ACT_Rmax485B+") (pin "2") (pinfunction "2_2") (pintype "passive"))
      (node (ref "ACT_RpuMAX485") (pin "2") (pinfunction "2_2") (pintype "passive"))
      (node (ref "ACT_RpuMax485dif") (pin "2") (pinfunction "2_2") (pintype "passive"))
      (node (ref "ACT_STM32F4DISCOVERY") (pin "53") (pinfunction "5V_53") (pintype "passive"))
      (node (ref "ACT_STM32F4DISCOVERY") (pin "54") (pinfunction "5V_54") (pintype "passive"))
      (node (ref "ACT_Ucan") (pin "3") (pinfunction "VDD_3") (pintype "power_in"))
      (node (ref "ACT_cod1") (pin "1") (pinfunction "1_1") (pintype "passive"))
      (node (ref "ACT_cod1") (pin "2") (pinfunction "2_2") (pintype "passive"))
      (node (ref "ACT_cod2") (pin "1") (pinfunction "1_1") (pintype "passive"))
      (node (ref "ACT_cod2") (pin "2") (pinfunction "2_2") (pintype "passive"))
      (node (ref "ACT_cod3") (pin "1") (pinfunction "1_1") (pintype "passive"))
      (node (ref "ACT_cod3") (pin "2") (pinfunction "2_2") (pintype "passive"))
      (node (ref "ACT_cod4") (pin "1") (pinfunction "1_1") (pintype "passive"))
      (node (ref "ACT_cod4") (pin "2") (pinfunction "2_2") (pintype "passive"))
    )
    (net (code "68") (name "5V_Perm") (class "Default")
      (node (ref "ACT_UART1") (pin "1") (pinfunction "1_1") (pintype "passive"))
      (node (ref "ACT_UART1") (pin "2") (pinfunction "2_2") (pintype "passive"))
    )
    (net (code "69") (name "5V_servos") (class "Default")
      (node (ref "Servo0") (pin "2") (pinfunction "2_2") (pintype "passive"))
      (node (ref "Servo1") (pin "2") (pinfunction "2_2") (pintype "passive"))
      (node (ref "Servo2") (pin "2") (pinfunction "2_2") (pintype "passive"))
      (node (ref "Servo3") (pin "2") (pinfunction "2_2") (pintype "passive"))
      (node (ref "Servo4") (pin "2") (pinfunction "2_2") (pintype "passive"))
      (node (ref "Servo5") (pin "2") (pinfunction "2_2") (pintype "passive"))
    )
    (net (code "70") (name "12V") (class "Default")
      (node (ref "ACT_AX12_1") (pin "2") (pinfunction "2_2") (pintype "passive"))
      (node (ref "ACT_AX12_2") (pin "2") (pinfunction "2_2") (pintype "passive"))
      (node (ref "ACT_RX24") (pin "3") (pinfunction "3_3") (pintype "passive"))
      (node (ref "ACT_RX24_2") (pin "3") (pinfunction "3_3") (pintype "passive"))
    )
    (net (code "71") (name "24V") (class "Default")
      (node (ref "ACT_AN11") (pin "3") (pinfunction "3_3") (pintype "passive"))
      (node (ref "ACT_AN12") (pin "3") (pinfunction "3_3") (pintype "passive"))
      (node (ref "ACT_AN13") (pin "3") (pinfunction "3_3") (pintype "passive"))
      (node (ref "ACT_AN7") (pin "3") (pinfunction "3_3") (pintype "passive"))
      (node (ref "ACT_AN8") (pin "3") (pinfunction "3_3") (pintype "passive"))
      (node (ref "ACT_AN9") (pin "3") (pinfunction "3_3") (pintype "passive"))
      (node (ref "ACT_CdAN11") (pin "2") (pinfunction "2_2") (pintype "passive"))
      (node (ref "ACT_CdAN12") (pin "2") (pinfunction "2_2") (pintype "passive"))
      (node (ref "ACT_CdAN13") (pin "2") (pinfunction "2_2") (pintype "passive"))
      (node (ref "ACT_CdAN7") (pin "2") (pinfunction "2_2") (pintype "passive"))
      (node (ref "ACT_CdAN8") (pin "2") (pinfunction "2_2") (pintype "passive"))
      (node (ref "ACT_CdAN9") (pin "2") (pinfunction "2_2") (pintype "passive"))
    )
    (net (code "72") (name "GND") (class "Default")
      (node (ref "ACT_Ccod1A") (pin "1") (pinfunction "1_1") (pintype "passive"))
      (node (ref "ACT_Ccod1B") (pin "1") (pinfunction "1_1") (pintype "passive"))
      (node (ref "ACT_Ccod2A") (pin "1") (pinfunction "1_1") (pintype "passive"))
      (node (ref "ACT_Ccod2B") (pin "1") (pinfunction "1_1") (pintype "passive"))
      (node (ref "ACT_Ccod3A") (pin "1") (pinfunction "1_1") (pintype "passive"))
      (node (ref "ACT_Ccod3B") (pin "1") (pinfunction "1_1") (pintype "passive"))
      (node (ref "ACT_Ccod4A") (pin "1") (pinfunction "1_1") (pintype "passive"))
      (node (ref "ACT_Ccod4B") (pin "1") (pinfunction "1_1") (pintype "passive"))
      (node (ref "ACT_CdCan1") (pin "1") (pinfunction "1_1") (pintype "passive"))
      (node (ref "ACT_CdCan2") (pin "1") (pinfunction "1_1") (pintype "passive"))
      (node (ref "ACT_CdMax485") (pin "1") (pinfunction "1_1") (pintype "passive"))
      (node (ref "ACT_CdMax485dif") (pin "1") (pinfunction "1_1") (pintype "passive"))
      (node (ref "ACT_CfAn11") (pin "1") (pinfunction "1_1") (pintype "passive"))
      (node (ref "ACT_CfAn12") (pin "1") (pinfunction "1_1") (pintype "passive"))
      (node (ref "ACT_CfAn13") (pin "1") (pinfunction "1_1") (pintype "passive"))
      (node (ref "ACT_CfAn14") (pin "1") (pinfunction "1_1") (pintype "passive"))
      (node (ref "ACT_CfAn15") (pin "1") (pinfunction "1_1") (pintype "passive"))
      (node (ref "ACT_CfAn7") (pin "1") (pinfunction "1_1") (pintype "passive"))
      (node (ref "ACT_CfAn8") (pin "1") (pinfunction "1_1") (pintype "passive"))
      (node (ref "ACT_CfAn9") (pin "1") (pinfunction "1_1") (pintype "passive"))
      (node (ref "ACT_Cu1rx") (pin "1") (pinfunction "1_1") (pintype "passive"))
      (node (ref "ACT_DSelftest") (pin "2") (pinfunction "K_2") (pintype "passive"))
      (node (ref "ACT_Derror") (pin "2") (pinfunction "K_2") (pintype "passive"))
      (node (ref "ACT_MAX485") (pin "5") (pinfunction "GND_5") (pintype "passive"))
      (node (ref "ACT_MAX485dif") (pin "5") (pinfunction "GND_5") (pintype "passive"))
      (node (ref "ACT_RFU") (pin "1") (pinfunction "1_1") (pintype "passive"))
      (node (ref "ACT_RdwnAn11") (pin "1") (pinfunction "1_1") (pintype "passive"))
      (node (ref "ACT_RdwnAn12") (pin "1") (pinfunction "1_1") (pintype "passive"))
      (node (ref "ACT_RdwnAn13") (pin "1") (pinfunction "1_1") (pintype "passive"))
      (node (ref "ACT_RdwnAn7") (pin "1") (pinfunction "1_1") (pintype "passive"))
      (node (ref "ACT_RdwnAn8") (pin "1") (pinfunction "1_1") (pintype "passive"))
      (node (ref "ACT_RdwnAn9") (pin "1") (pinfunction "1_1") (pintype "passive"))
      (node (ref "ACT_RdwnWAmI") (pin "1") (pinfunction "1_1") (pintype "passive"))
      (node (ref "ACT_Rmax485B-") (pin "1") (pinfunction "1_1") (pintype "passive"))
      (node (ref "ACT_STM32F4DISCOVERY") (pin "1") (pinfunction "GND_1") (pintype "passive"))
      (node (ref "ACT_STM32F4DISCOVERY") (pin "100") (pinfunction "GND_100") (pintype "passive"))
      (node (ref "ACT_STM32F4DISCOVERY") (pin "2") (pinfunction "GND_2") (pintype "passive"))
      (node (ref "ACT_STM32F4DISCOVERY") (pin "23") (pinfunction "GND_23") (pintype "passive"))
      (node (ref "ACT_STM32F4DISCOVERY") (pin "49") (pinfunction "GND_49") (pintype "passive"))
      (node (ref "ACT_STM32F4DISCOVERY") (pin "5") (pinfunction "GND_5") (pintype "passive"))
      (node (ref "ACT_STM32F4DISCOVERY") (pin "50") (pinfunction "GND_50") (pintype "passive"))
      (node (ref "ACT_STM32F4DISCOVERY") (pin "51") (pinfunction "GND_51") (pintype "passive"))
      (node (ref "ACT_STM32F4DISCOVERY") (pin "52") (pinfunction "GND_52") (pintype "passive"))
      (node (ref "ACT_STM32F4DISCOVERY") (pin "99") (pinfunction "GND_99") (pintype "passive"))
      (node (ref "ACT_UART1") (pin "5") (pinfunction "5_5") (pintype "passive"))
      (node (ref "ACT_UART1") (pin "6") (pinfunction "6_6") (pintype "passive"))
      (node (ref "ACT_Ucan") (pin "2") (pinfunction "VSS_2") (pintype "power_in"))
      (node (ref "ACT_Ucan") (pin "8") (pinfunction "RS_8") (pintype "input"))
      (node (ref "ACT__Mot12") (pin "3") (pinfunction "3_3") (pintype "passive"))
      (node (ref "ACT__Mot12") (pin "4") (pinfunction "4_4") (pintype "passive"))
      (node (ref "ACT_cod1") (pin "5") (pinfunction "5_5") (pintype "passive"))
      (node (ref "ACT_cod1") (pin "6") (pinfunction "6_6") (pintype "passive"))
      (node (ref "ACT_cod2") (pin "5") (pinfunction "5_5") (pintype "passive"))
      (node (ref "ACT_cod2") (pin "6") (pinfunction "6_6") (pintype "passive"))
      (node (ref "ACT_cod3") (pin "5") (pinfunction "5_5") (pintype "passive"))
      (node (ref "ACT_cod3") (pin "6") (pinfunction "6_6") (pintype "passive"))
      (node (ref "ACT_cod4") (pin "5") (pinfunction "5_5") (pintype "passive"))
      (node (ref "ACT_cod4") (pin "6") (pinfunction "6_6") (pintype "passive"))
      (node (ref "ACT_currentMot") (pin "1") (pinfunction "1_1") (pintype "passive"))
      (node (ref "ACT_mot34") (pin "3") (pinfunction "3_3") (pintype "passive"))
      (node (ref "ACT_mot34") (pin "4") (pinfunction "4_4") (pintype "passive"))
      (node (ref "ACT_stAN11") (pin "3") (pinfunction "3_3") (pintype "passive"))
      (node (ref "ACT_stAN12") (pin "3") (pinfunction "3_3") (pintype "passive"))
      (node (ref "ACT_stAN13") (pin "3") (pinfunction "3_3") (pintype "passive"))
      (node (ref "ACT_stAN7") (pin "3") (pinfunction "3_3") (pintype "passive"))
      (node (ref "ACT_stAN9") (pin "3") (pinfunction "3_3") (pintype "passive"))
      (node (ref "TOR") (pin "1") (pinfunction "1_1") (pintype "passive"))
      (node (ref "st_i_am_a") (pin "1") (pinfunction "1_1") (pintype "passive"))
    )
    (net (code "73") (name "GND_5") (class "Default")
      (node (ref "Servo0") (pin "1") (pinfunction "1_1") (pintype "passive"))
      (node (ref "Servo1") (pin "1") (pinfunction "1_1") (pintype "passive"))
      (node (ref "Servo2") (pin "1") (pinfunction "1_1") (pintype "passive"))
      (node (ref "Servo3") (pin "1") (pinfunction "1_1") (pintype "passive"))
      (node (ref "Servo4") (pin "1") (pinfunction "1_1") (pintype "passive"))
      (node (ref "Servo5") (pin "1") (pinfunction "1_1") (pintype "passive"))
    )
    (net (code "74") (name "GND_12") (class "Default")
      (node (ref "ACT_AX12_1") (pin "3") (pinfunction "3_3") (pintype "passive"))
      (node (ref "ACT_AX12_2") (pin "3") (pinfunction "3_3") (pintype "passive"))
      (node (ref "ACT_RX24") (pin "4") (pinfunction "4_4") (pintype "passive"))
      (node (ref "ACT_RX24_2") (pin "4") (pinfunction "4_4") (pintype "passive"))
    )
    (net (code "75") (name "GND_24") (class "Default")
      (node (ref "ACT_AN8") (pin "1") (pinfunction "1_1") (pintype "passive"))
      (node (ref "ACT_CdAN11") (pin "1") (pinfunction "1_1") (pintype "passive"))
      (node (ref "ACT_CdAN12") (pin "1") (pinfunction "1_1") (pintype "passive"))
      (node (ref "ACT_CdAN13") (pin "1") (pinfunction "1_1") (pintype "passive"))
      (node (ref "ACT_CdAN7") (pin "1") (pinfunction "1_1") (pintype "passive"))
      (node (ref "ACT_CdAN8") (pin "1") (pinfunction "1_1") (pintype "passive"))
      (node (ref "ACT_CdAN9") (pin "1") (pinfunction "1_1") (pintype "passive"))
      (node (ref "ACT_stAN11") (pin "1") (pinfunction "1_1") (pintype "passive"))
      (node (ref "ACT_stAN12") (pin "1") (pinfunction "1_1") (pintype "passive"))
      (node (ref "ACT_stAN13") (pin "1") (pinfunction "1_1") (pintype "passive"))
      (node (ref "ACT_stAN7") (pin "1") (pinfunction "1_1") (pintype "passive"))
      (node (ref "ACT_stAN9") (pin "1") (pinfunction "1_1") (pintype "passive"))
    )
    (net (code "76") (name "Net-(ACT_AN7-Pad1)") (class "Default")
      (node (ref "ACT_AN7") (pin "1") (pinfunction "1_1") (pintype "passive"))
      (node (ref "ACT_stAN7") (pin "2") (pinfunction "2_2") (pintype "passive"))
    )
    (net (code "77") (name "Net-(ACT_AN7-Pad2)") (class "Default")
      (node (ref "ACT_AN7") (pin "2") (pinfunction "2_2") (pintype "passive"))
      (node (ref "ACT_RdwnAn7") (pin "2") (pinfunction "2_2") (pintype "passive"))
      (node (ref "ACT_RfAn7") (pin "2") (pinfunction "2_2") (pintype "passive"))
    )
    (net (code "78") (name "Net-(ACT_AN8-Pad2)") (class "Default")
      (node (ref "ACT_AN8") (pin "2") (pinfunction "2_2") (pintype "passive"))
      (node (ref "ACT_RdwnAn8") (pin "2") (pinfunction "2_2") (pintype "passive"))
      (node (ref "ACT_RfAn8") (pin "2") (pinfunction "2_2") (pintype "passive"))
    )
    (net (code "79") (name "Net-(ACT_AN9-Pad1)") (class "Default")
      (node (ref "ACT_AN9") (pin "1") (pinfunction "1_1") (pintype "passive"))
      (node (ref "ACT_stAN9") (pin "2") (pinfunction "2_2") (pintype "passive"))
    )
    (net (code "80") (name "Net-(ACT_AN9-Pad2)") (class "Default")
      (node (ref "ACT_AN9") (pin "2") (pinfunction "2_2") (pintype "passive"))
      (node (ref "ACT_RdwnAn9") (pin "2") (pinfunction "2_2") (pintype "passive"))
      (node (ref "ACT_RfAn9") (pin "2") (pinfunction "2_2") (pintype "passive"))
    )
    (net (code "81") (name "Net-(ACT_AN11-Pad1)") (class "Default")
      (node (ref "ACT_AN11") (pin "1") (pinfunction "1_1") (pintype "passive"))
      (node (ref "ACT_stAN11") (pin "2") (pinfunction "2_2") (pintype "passive"))
    )
    (net (code "82") (name "Net-(ACT_AN11-Pad2)") (class "Default")
      (node (ref "ACT_AN11") (pin "2") (pinfunction "2_2") (pintype "passive"))
      (node (ref "ACT_RdwnAn11") (pin "2") (pinfunction "2_2") (pintype "passive"))
      (node (ref "ACT_RfAn11") (pin "2") (pinfunction "2_2") (pintype "passive"))
    )
    (net (code "83") (name "Net-(ACT_AN12-Pad1)") (class "Default")
      (node (ref "ACT_AN12") (pin "1") (pinfunction "1_1") (pintype "passive"))
      (node (ref "ACT_stAN12") (pin "2") (pinfunction "2_2") (pintype "passive"))
    )
    (net (code "84") (name "Net-(ACT_AN12-Pad2)") (class "Default")
      (node (ref "ACT_AN12") (pin "2") (pinfunction "2_2") (pintype "passive"))
      (node (ref "ACT_RdwnAn12") (pin "2") (pinfunction "2_2") (pintype "passive"))
      (node (ref "ACT_RfAn12") (pin "2") (pinfunction "2_2") (pintype "passive"))
    )
    (net (code "85") (name "Net-(ACT_AN13-Pad1)") (class "Default")
      (node (ref "ACT_AN13") (pin "1") (pinfunction "1_1") (pintype "passive"))
      (node (ref "ACT_stAN13") (pin "2") (pinfunction "2_2") (pintype "passive"))
    )
    (net (code "86") (name "Net-(ACT_AN13-Pad2)") (class "Default")
      (node (ref "ACT_AN13") (pin "2") (pinfunction "2_2") (pintype "passive"))
      (node (ref "ACT_RdwnAn13") (pin "2") (pinfunction "2_2") (pintype "passive"))
      (node (ref "ACT_RfAn13") (pin "2") (pinfunction "2_2") (pintype "passive"))
    )
    (net (code "87") (name "Net-(ACT_DSelftest-A)") (class "Default")
      (node (ref "ACT_DSelftest") (pin "1") (pinfunction "A_1") (pintype "passive"))
      (node (ref "ACT_Rdselftest") (pin "2") (pinfunction "2_2") (pintype "passive"))
    )
    (net (code "88") (name "Net-(ACT_Derror-A)") (class "Default")
      (node (ref "ACT_Derror") (pin "1") (pinfunction "A_1") (pintype "passive"))
      (node (ref "ACT_Rderror") (pin "2") (pinfunction "2_2") (pintype "passive"))
    )
    (net (code "89") (name "Net-(ACT_MAX485-~{B})") (class "Default")
      (node (ref "ACT_MAX485") (pin "7") (pinfunction "~{B}_7") (pintype "bidirectional"))
      (node (ref "ACT_Rmax485B+") (pin "1") (pinfunction "1_1") (pintype "passive"))
      (node (ref "ACT_Rmax485B-") (pin "2") (pinfunction "2_2") (pintype "passive"))
    )
    (net (code "90") (name "Net-(ACT_RCod1A-Pad2)") (class "Default")
      (node (ref "ACT_RCod1A") (pin "2") (pinfunction "2_2") (pintype "passive"))
      (node (ref "ACT_cod1") (pin "3") (pinfunction "3_3") (pintype "passive"))
    )
    (net (code "91") (name "Net-(ACT_RCod1B-Pad2)") (class "Default")
      (node (ref "ACT_RCod1B") (pin "2") (pinfunction "2_2") (pintype "passive"))
      (node (ref "ACT_cod1") (pin "4") (pinfunction "4_4") (pintype "passive"))
    )
    (net (code "92") (name "Net-(ACT_RCod2A-Pad2)") (class "Default")
      (node (ref "ACT_RCod2A") (pin "2") (pinfunction "2_2") (pintype "passive"))
      (node (ref "ACT_cod2") (pin "3") (pinfunction "3_3") (pintype "passive"))
    )
    (net (code "93") (name "Net-(ACT_RCod2B-Pad2)") (class "Default")
      (node (ref "ACT_RCod2B") (pin "2") (pinfunction "2_2") (pintype "passive"))
      (node (ref "ACT_cod2") (pin "4") (pinfunction "4_4") (pintype "passive"))
    )
    (net (code "94") (name "Net-(ACT_RCod3A-Pad2)") (class "Default")
      (node (ref "ACT_RCod3A") (pin "2") (pinfunction "2_2") (pintype "passive"))
      (node (ref "ACT_cod3") (pin "3") (pinfunction "3_3") (pintype "passive"))
    )
    (net (code "95") (name "Net-(ACT_RCod3B-Pad2)") (class "Default")
      (node (ref "ACT_RCod3B") (pin "2") (pinfunction "2_2") (pintype "passive"))
      (node (ref "ACT_cod3") (pin "4") (pinfunction "4_4") (pintype "passive"))
    )
    (net (code "96") (name "Net-(ACT_RCod4A-Pad2)") (class "Default")
      (node (ref "ACT_RCod4A") (pin "2") (pinfunction "2_2") (pintype "passive"))
      (node (ref "ACT_cod4") (pin "3") (pinfunction "3_3") (pintype "passive"))
    )
    (net (code "97") (name "Net-(ACT_RCod4B-Pad2)") (class "Default")
      (node (ref "ACT_RCod4B") (pin "2") (pinfunction "2_2") (pintype "passive"))
      (node (ref "ACT_cod4") (pin "4") (pinfunction "4_4") (pintype "passive"))
    )
    (net (code "98") (name "Net-(ACT_RfAn14-Pad2)") (class "Default")
      (node (ref "ACT_RfAn14") (pin "2") (pinfunction "2_2") (pintype "passive"))
      (node (ref "ACT_currentMot") (pin "3") (pinfunction "3_3") (pintype "passive"))
    )
    (net (code "99") (name "Net-(ACT_RfAn15-Pad2)") (class "Default")
      (node (ref "ACT_RfAn15") (pin "2") (pinfunction "2_2") (pintype "passive"))
      (node (ref "ACT_currentMot") (pin "2") (pinfunction "2_2") (pintype "passive"))
    )
    (net (code "100") (name "unconnected-(ACT_RFU-Pad4)") (class "Default")
      (node (ref "ACT_RFU") (pin "4") (pinfunction "4_4") (pintype "passive"))
    )
    (net (code "101") (name "unconnected-(ACT_STM32F4DISCOVERY-BOOT0{slash}VPP-Pad71)") (class "Default")
      (node (ref "ACT_STM32F4DISCOVERY") (pin "71") (pinfunction "BOOT0/VPP_71") (pintype "passive+no_connect"))
    )
    (net (code "102") (name "unconnected-(ACT_STM32F4DISCOVERY-NC-Pad48)") (class "Default")
      (node (ref "ACT_STM32F4DISCOVERY") (pin "48") (pinfunction "NC_48") (pintype "passive+no_connect"))
    )
    (net (code "103") (name "unconnected-(ACT_STM32F4DISCOVERY-NRST-Pad6)") (class "Default")
      (node (ref "ACT_STM32F4DISCOVERY") (pin "6") (pinfunction "NRST_6") (pintype "passive+no_connect"))
    )
    (net (code "104") (name "unconnected-(ACT_STM32F4DISCOVERY-PA0-WKUP{slash}USART2_CTS{slash}USART4_TX{slash}ETH_MII_CRS{slash}TIM2_CH1_ETR{slash}TIM5_CH1{slash}TIM8_ETR{slash}ADC123_IN0{slash}WKUP-Pad12)") (class "Default")
      (node (ref "ACT_STM32F4DISCOVERY") (pin "12") (pinfunction "PA0-WKUP/USART2_CTS/USART4_TX/ETH_MII_CRS/TIM2_CH1_ETR/TIM5_CH1/TIM8_ETR/ADC123_IN0/WKUP_12") (pintype "passive+no_connect"))
    )
    (net (code "105") (name "unconnected-(ACT_STM32F4DISCOVERY-PA4{slash}SPI1_NSS{slash}SPI3_NSS{slash}USART2_CK{slash}DCMI_HSYNC{slash}OTG_HS_SOF{slash}I2S3_WS{slash}ADC12_IN4{slash}DAC1_OUT-Pad16)") (class "Default")
      (node (ref "ACT_STM32F4DISCOVERY") (pin "16") (pinfunction "PA4/SPI1_NSS/SPI3_NSS/USART2_CK/DCMI_HSYNC/OTG_HS_SOF/I2S3_WS/ADC12_IN4/DAC1_OUT_16") (pintype "passive+no_connect"))
    )
    (net (code "106") (name "unconnected-(ACT_STM32F4DISCOVERY-PA6{slash}SPI1_MISO{slash}TIM8_BKIN{slash}TIM13_CH1{slash}DCMI_PIXCLK{slash}TIM3_CH1{slash}TIM1_BKIN{slash}ADC12_IN6-Pad18)") (class "Default")
      (node (ref "ACT_STM32F4DISCOVERY") (pin "18") (pinfunction "PA6/SPI1_MISO/TIM8_BKIN/TIM13_CH1/DCMI_PIXCLK/TIM3_CH1/TIM1_BKIN/ADC12_IN6_18") (pintype "passive+no_connect"))
    )
    (net (code "107") (name "unconnected-(ACT_STM32F4DISCOVERY-PA9{slash}USART1_TX{slash}TIM1_CH2{slash}I2C3_SMBA{slash}DCMI_D0{slash}OTG_FS_VBUS-Pad94)") (class "Default")
      (node (ref "ACT_STM32F4DISCOVERY") (pin "94") (pinfunction "PA9/USART1_TX/TIM1_CH2/I2C3_SMBA/DCMI_D0/OTG_FS_VBUS_94") (pintype "passive+no_connect"))
    )
    (net (code "108") (name "unconnected-(ACT_STM32F4DISCOVERY-PA10{slash}USART1_RX{slash}TIM1_CH3{slash}OTG_FS_ID{slash}DCMI_D1-Pad91)") (class "Default")
      (node (ref "ACT_STM32F4DISCOVERY") (pin "91") (pinfunction "PA10/USART1_RX/TIM1_CH3/OTG_FS_ID/DCMI_D1_91") (pintype "passive+no_connect"))
    )
    (net (code "109") (name "unconnected-(ACT_STM32F4DISCOVERY-PA13{slash}JTMS_SWDIO-Pad92)") (class "Default")
      (node (ref "ACT_STM32F4DISCOVERY") (pin "92") (pinfunction "PA13/JTMS_SWDIO_92") (pintype "passive+no_connect"))
    )
    (net (code "110") (name "unconnected-(ACT_STM32F4DISCOVERY-PA14{slash}JTCK_SWCLK-Pad89)") (class "Default")
      (node (ref "ACT_STM32F4DISCOVERY") (pin "89") (pinfunction "PA14/JTCK_SWCLK_89") (pintype "passive+no_connect"))
    )
    (net (code "111") (name "unconnected-(ACT_STM32F4DISCOVERY-PB3{slash}JTDO{slash}TRACESWO{slash}SPI3_SCK{slash}I2S3_CK{slash}TIM2_CH2{slash}SPI1_SCK-Pad78)") (class "Default")
      (node (ref "ACT_STM32F4DISCOVERY") (pin "78") (pinfunction "PB3/JTDO/TRACESWO/SPI3_SCK/I2S3_CK/TIM2_CH2/SPI1_SCK_78") (pintype "passive+no_connect"))
    )
    (net (code "112") (name "unconnected-(ACT_STM32F4DISCOVERY-PC0{slash}OTG_HS_ULPI_STP{slash}ADC123_IN10-Pad8)") (class "Default")
      (node (ref "ACT_STM32F4DISCOVERY") (pin "8") (pinfunction "PC0/OTG_HS_ULPI_STP/ADC123_IN10_8") (pintype "passive+no_connect"))
    )
    (net (code "113") (name "unconnected-(ACT_STM32F4DISCOVERY-PC14{slash}OSC32_IN-Pad59)") (class "Default")
      (node (ref "ACT_STM32F4DISCOVERY") (pin "59") (pinfunction "PC14/OSC32_IN_59") (pintype "passive+no_connect"))
    )
    (net (code "114") (name "unconnected-(ACT_STM32F4DISCOVERY-PC15{slash}OSC32_OUT-Pad60)") (class "Default")
      (node (ref "ACT_STM32F4DISCOVERY") (pin "60") (pinfunction "PC15/OSC32_OUT_60") (pintype "passive+no_connect"))
    )
    (net (code "115") (name "unconnected-(ACT_STM32F4DISCOVERY-PD4{slash}FSMC_NOE{slash}USART2_RTS-Pad82)") (class "Default")
      (node (ref "ACT_STM32F4DISCOVERY") (pin "82") (pinfunction "PD4/FSMC_NOE/USART2_RTS_82") (pintype "passive+no_connect"))
    )
    (net (code "116") (name "unconnected-(ACT_STM32F4DISCOVERY-PD5{slash}FSMC_NWE{slash}USART2_TX-Pad79)") (class "Default")
      (node (ref "ACT_STM32F4DISCOVERY") (pin "79") (pinfunction "PD5/FSMC_NWE/USART2_TX_79") (pintype "passive+no_connect"))
    )
    (net (code "117") (name "unconnected-(ACT_STM32F4DISCOVERY-PE0{slash}TIM4_ETR{slash}FSMC_NBL0{slash}DCMI_D2-Pad67)") (class "Default")
      (node (ref "ACT_STM32F4DISCOVERY") (pin "67") (pinfunction "PE0/TIM4_ETR/FSMC_NBL0/DCMI_D2_67") (pintype "passive+no_connect"))
    )
    (net (code "118") (name "unconnected-(ACT_STM32F4DISCOVERY-PE1{slash}FSMC_NBL1{slash}DCMI_D3-Pad68)") (class "Default")
      (node (ref "ACT_STM32F4DISCOVERY") (pin "68") (pinfunction "PE1/FSMC_NBL1/DCMI_D3_68") (pintype "passive+no_connect"))
    )
    (net (code "119") (name "unconnected-(ACT_STM32F4DISCOVERY-PE2{slash}TRACECLK{slash}FSMC_A23{slash}ETH_MII_TXD3-Pad65)") (class "Default")
      (node (ref "ACT_STM32F4DISCOVERY") (pin "65") (pinfunction "PE2/TRACECLK/FSMC_A23/ETH_MII_TXD3_65") (pintype "passive+no_connect"))
    )
    (net (code "120") (name "unconnected-(ACT_STM32F4DISCOVERY-PE3{slash}TRACED0{slash}FSMC_A19-Pad66)") (class "Default")
      (node (ref "ACT_STM32F4DISCOVERY") (pin "66") (pinfunction "PE3/TRACED0/FSMC_A19_66") (pintype "passive+no_connect"))
    )
    (net (code "121") (name "unconnected-(ACT_STM32F4DISCOVERY-PE4{slash}TRACED1{slash}FSMC_A20{slash}DCMI_D4-Pad63)") (class "Default")
      (node (ref "ACT_STM32F4DISCOVERY") (pin "63") (pinfunction "PE4/TRACED1/FSMC_A20/DCMI_D4_63") (pintype "passive+no_connect"))
    )
    (net (code "122") (name "unconnected-(ACT_STM32F4DISCOVERY-PE7{slash}FSMC_D4{slash}TIM1_ETR-Pad25)") (class "Default")
      (node (ref "ACT_STM32F4DISCOVERY") (pin "25") (pinfunction "PE7/FSMC_D4/TIM1_ETR_25") (pintype "passive+no_connect"))
    )
    (net (code "123") (name "unconnected-(ACT_STM32F4DISCOVERY-PE9{slash}FSMC_D6{slash}TIM1_CH1-Pad27)") (class "Default")
      (node (ref "ACT_STM32F4DISCOVERY") (pin "27") (pinfunction "PE9/FSMC_D6/TIM1_CH1_27") (pintype "passive+no_connect"))
    )
    (net (code "124") (name "unconnected-(ACT_STM32F4DISCOVERY-PH0{slash}OSC_IN-Pad57)") (class "Default")
      (node (ref "ACT_STM32F4DISCOVERY") (pin "57") (pinfunction "PH0/OSC_IN_57") (pintype "passive+no_connect"))
    )
    (net (code "125") (name "unconnected-(ACT_STM32F4DISCOVERY-PH1{slash}OSC_OUT-Pad58)") (class "Default")
      (node (ref "ACT_STM32F4DISCOVERY") (pin "58") (pinfunction "PH1/OSC_OUT_58") (pintype "passive+no_connect"))
    )
    (net (code "126") (name "unconnected-(ACT_STM32F4DISCOVERY-VDD-Pad3)") (class "Default")
      (node (ref "ACT_STM32F4DISCOVERY") (pin "3") (pinfunction "VDD_3") (pintype "passive+no_connect"))
    )
    (net (code "127") (name "unconnected-(ACT_STM32F4DISCOVERY-VDD-Pad4)") (class "Default")
      (node (ref "ACT_STM32F4DISCOVERY") (pin "4") (pinfunction "VDD_4") (pintype "passive+no_connect"))
    )
    (net (code "128") (name "unconnected-(ACT_STM32F4DISCOVERY-VDD-Pad72)") (class "Default")
      (node (ref "ACT_STM32F4DISCOVERY") (pin "72") (pinfunction "VDD_72") (pintype "passive+no_connect"))
    )
    (net (code "129") (name "unconnected-(ACT_Ucan-VREF-Pad5)") (class "Default")
      (node (ref "ACT_Ucan") (pin "5") (pinfunction "VREF_5") (pintype "output"))
    )
  )
)
